# main.net
KiCad netlist of a schematic drawn in EAGLE
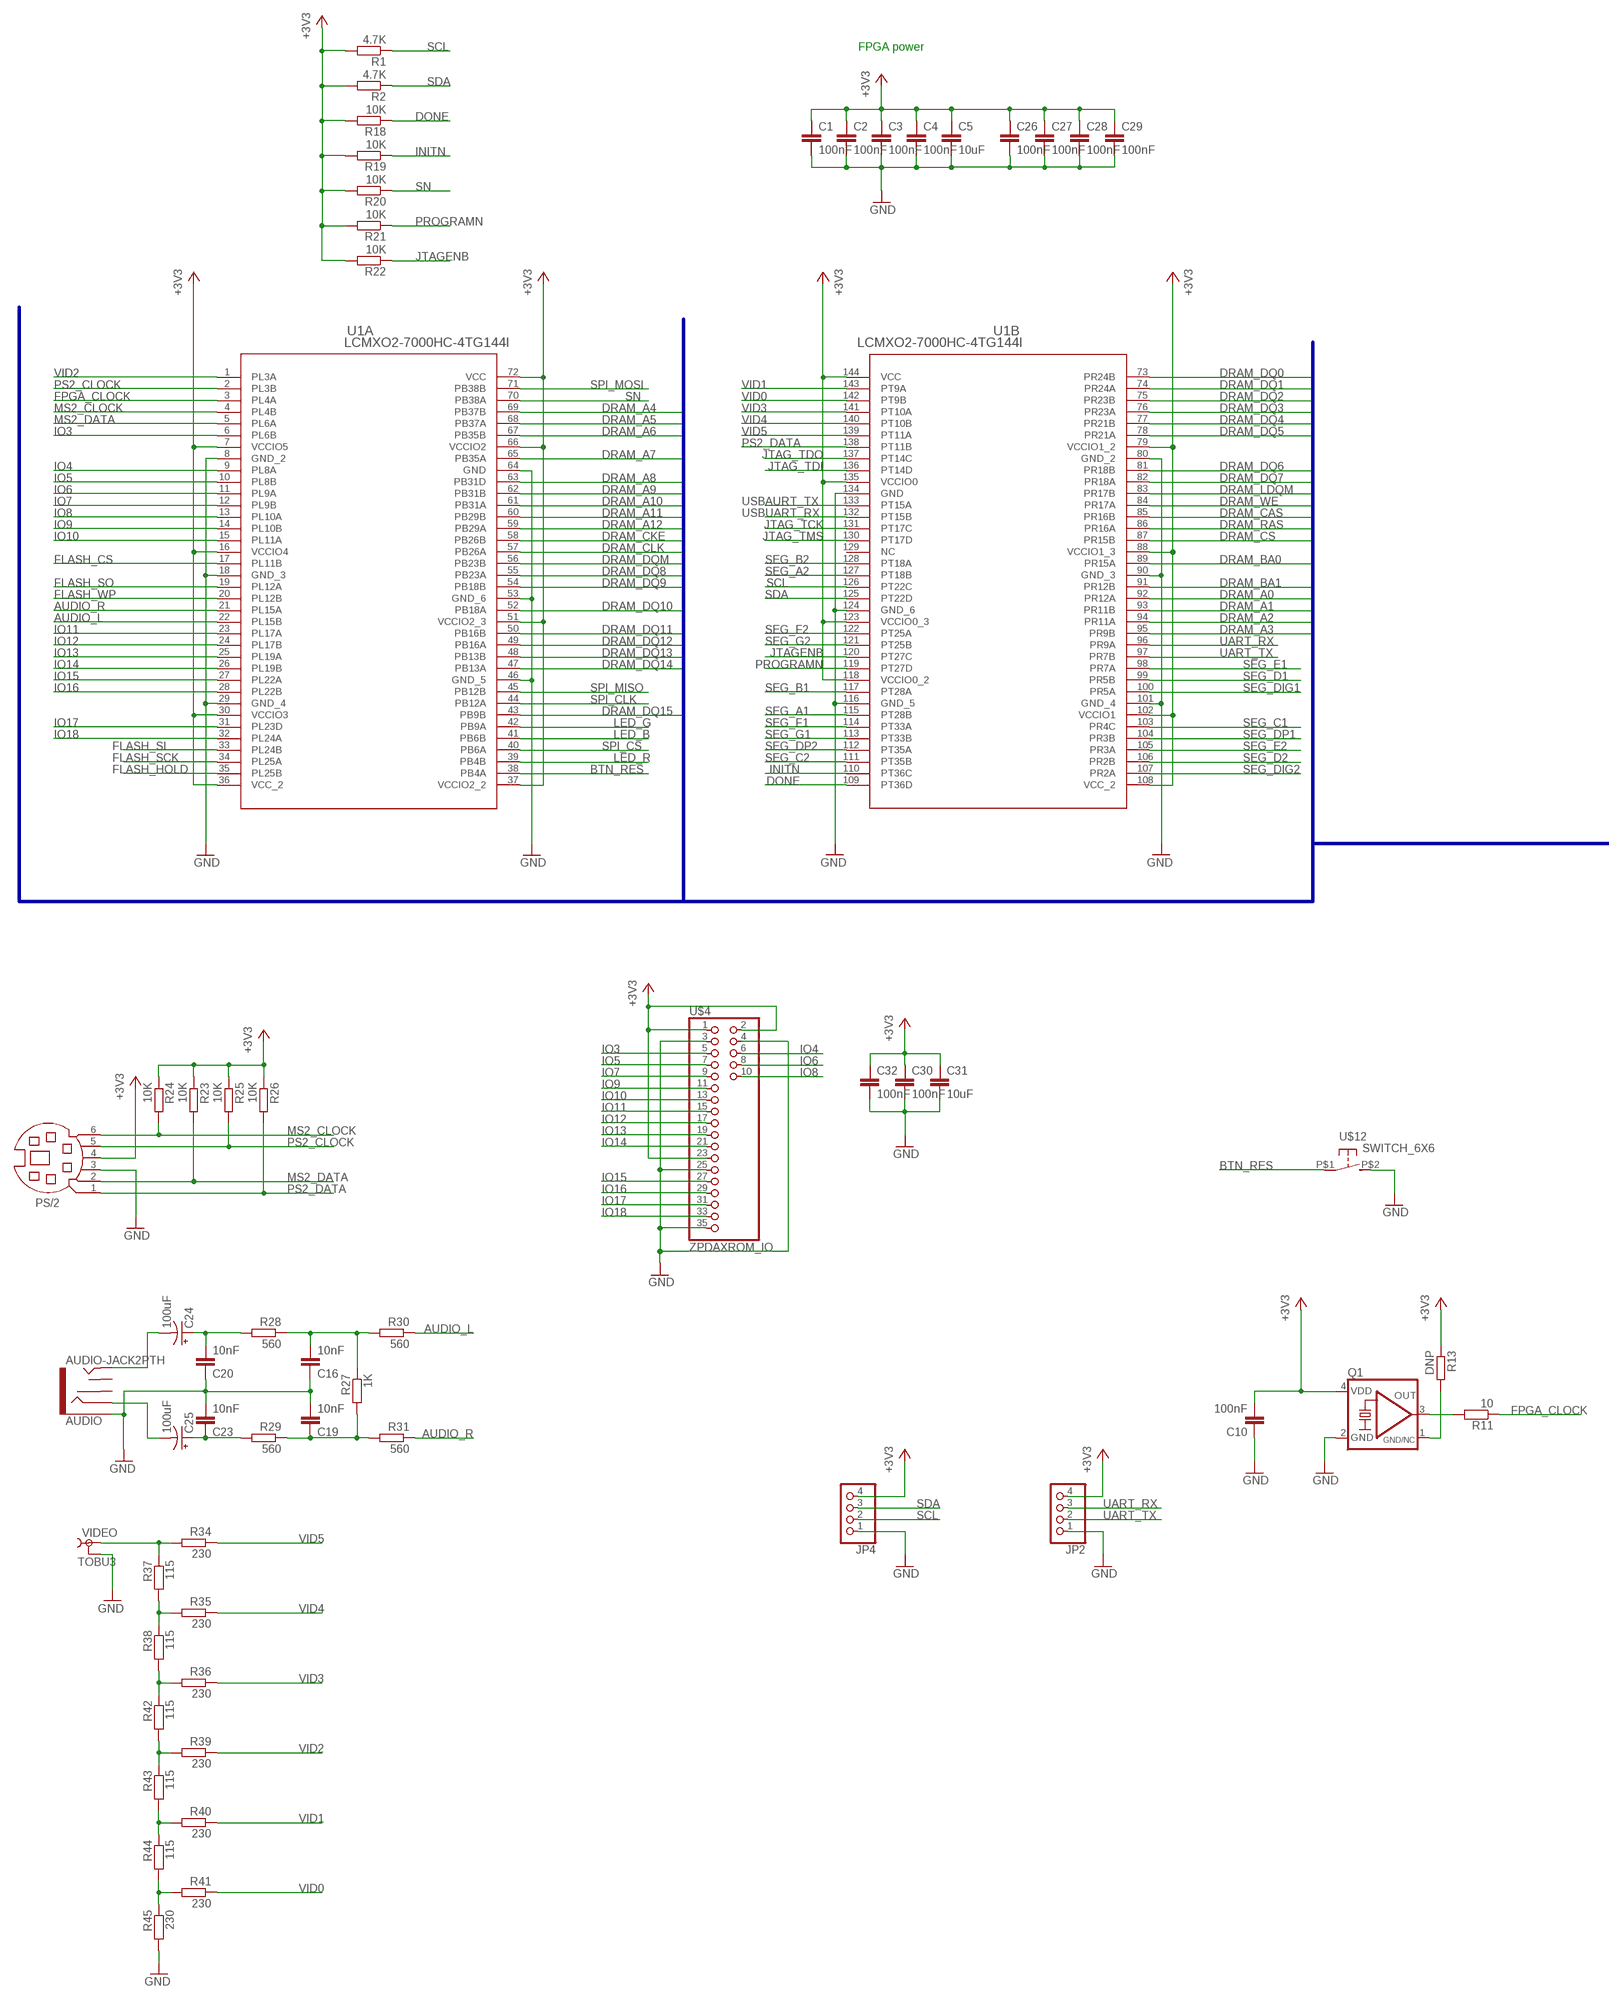
[diagram p0: schematic, sheet 1, part 1 of 2]
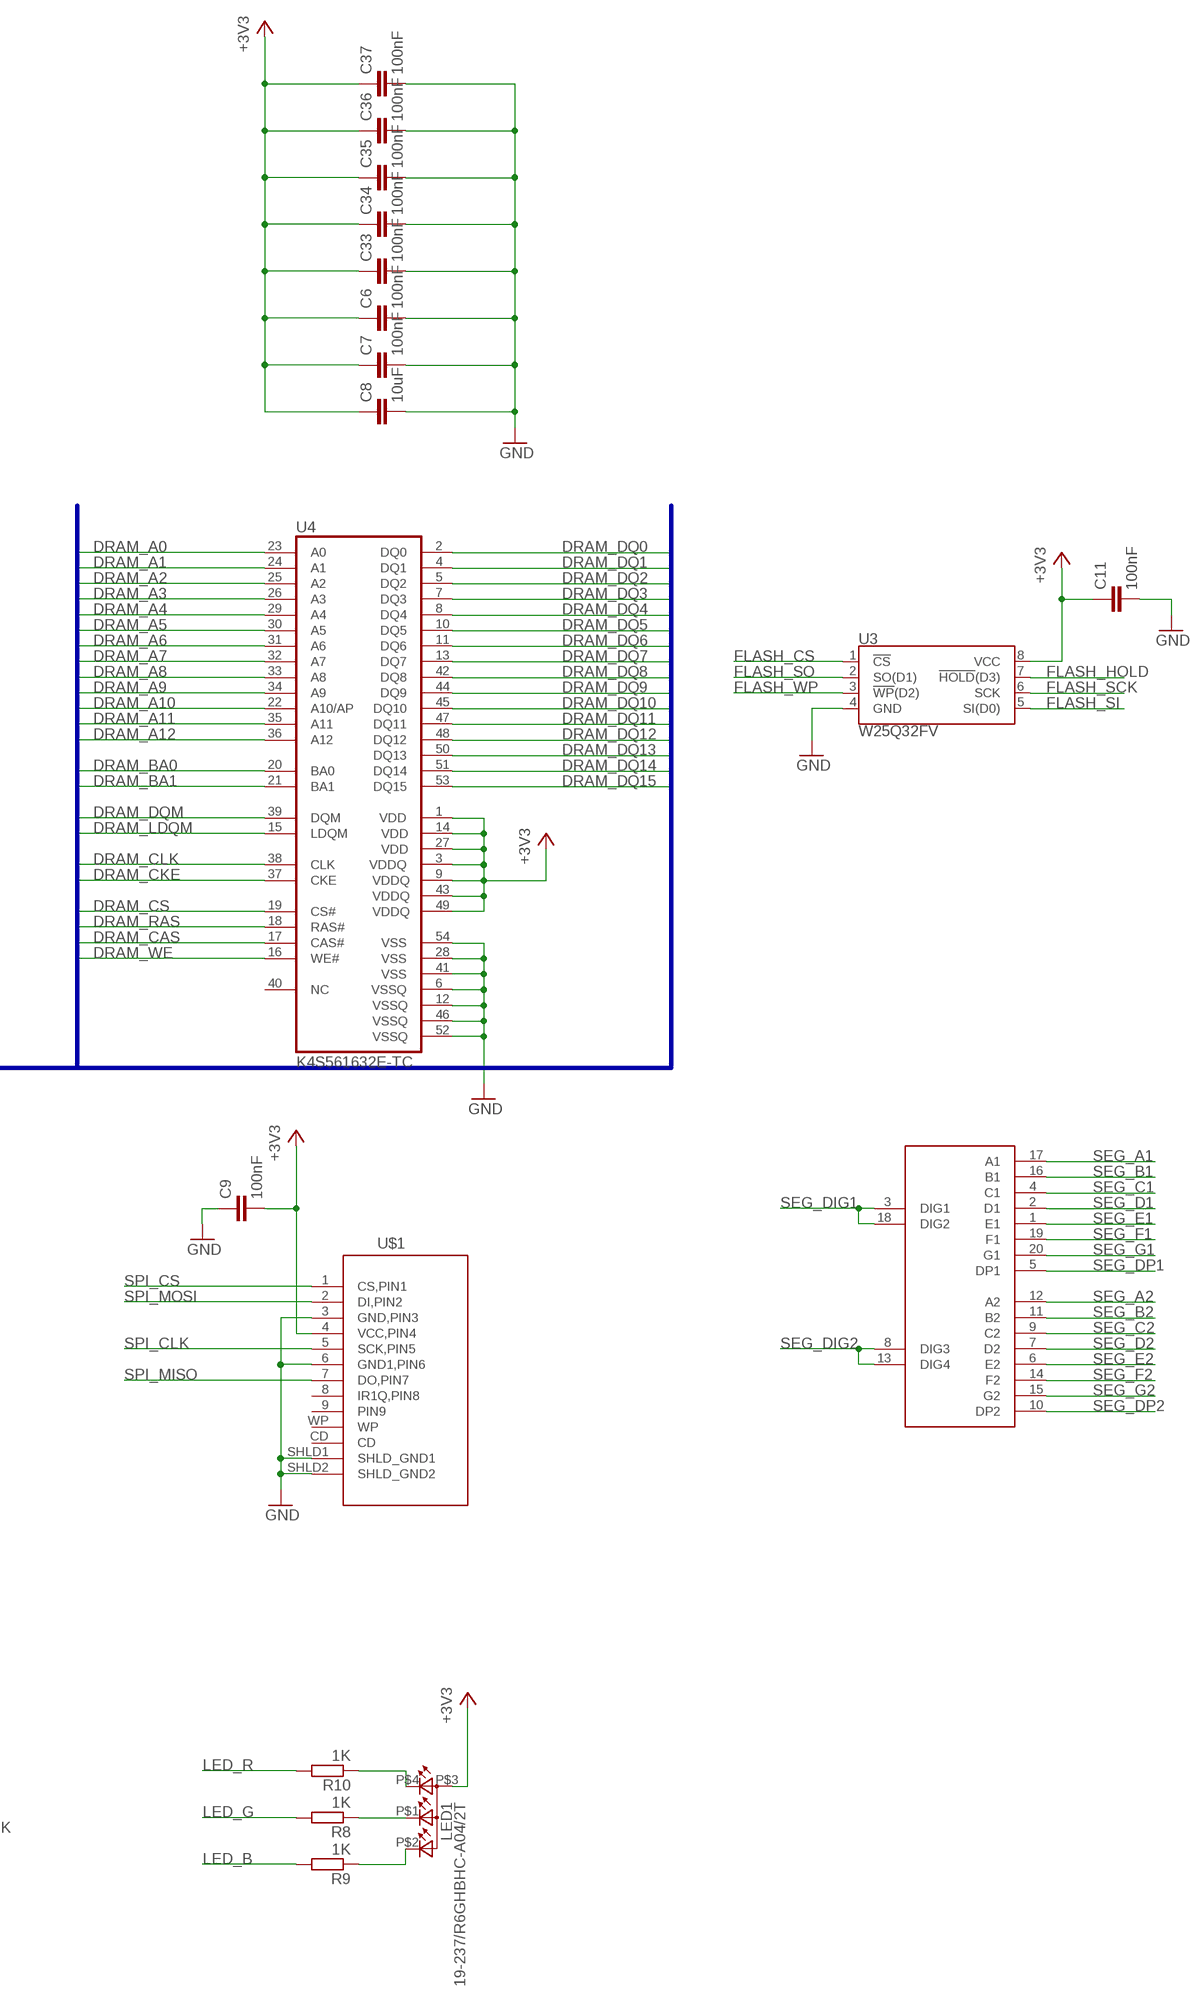
[diagram p1: schematic, sheet 1, part 2 of 2]
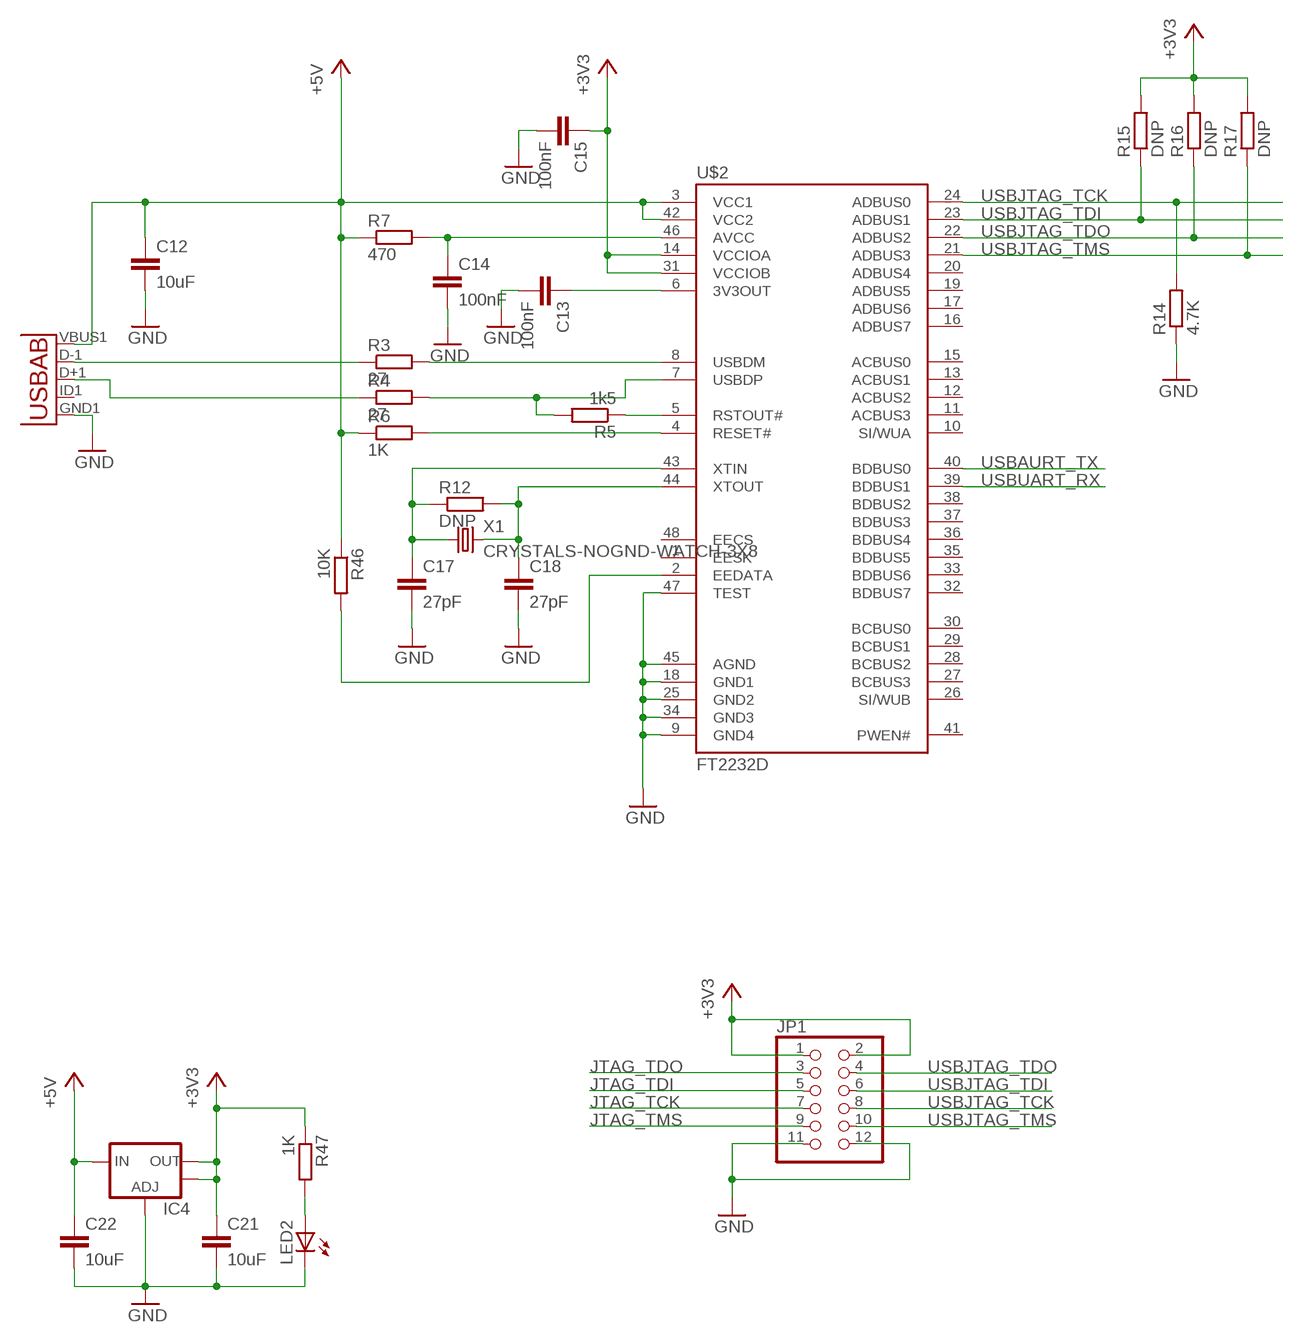
[diagram p2: schematic, sheet 2]

(export (version "E")
  (design (tool "Eeschema 10.0.6"))
  (components
    (comp (ref "C12")
      (value "10uF")
      (footprint "eagle-import:C0805")
      (libsource (lib "eagle-import") (part "C-EUC0805"))
    )
    (comp (ref "C13")
      (value "100nF")
      (footprint "eagle-import:C0603")
      (libsource (lib "eagle-import") (part "C-EUC0603"))
    )
    (comp (ref "C14")
      (value "100nF")
      (footprint "eagle-import:C0603")
      (libsource (lib "eagle-import") (part "C-EUC0603"))
    )
    (comp (ref "C15")
      (value "100nF")
      (footprint "eagle-import:C0603")
      (libsource (lib "eagle-import") (part "C-EUC0603"))
    )
    (comp (ref "C17")
      (value "27pF")
      (footprint "eagle-import:C0603")
      (libsource (lib "eagle-import") (part "C-EUC0603"))
    )
    (comp (ref "C18")
      (value "27pF")
      (footprint "eagle-import:C0603")
      (libsource (lib "eagle-import") (part "C-EUC0603"))
    )
    (comp (ref "C21")
      (value "10uF")
      (footprint "eagle-import:C0805")
      (libsource (lib "eagle-import") (part "C-EUC0805"))
    )
    (comp (ref "C22")
      (value "10uF")
      (footprint "eagle-import:C0805")
      (libsource (lib "eagle-import") (part "C-EUC0805"))
    )
    (comp (ref "IC4")
      (value "V_REG_LM1117SOT223")
      (footprint "eagle-import:SOT223")
      (libsource (lib "eagle-import") (part "V_REG_LM1117SOT223"))
    )
    (comp (ref "JP1")
      (value "PINHD-2X6")
      (footprint "eagle-import:2X06")
      (libsource (lib "eagle-import") (part "PINHD-2X6"))
    )
    (comp (ref "LED2")
      (value "LEDCHIPLED_0603")
      (footprint "eagle-import:CHIPLED_0603")
      (libsource (lib "eagle-import") (part "LEDCHIPLED_0603"))
    )
    (comp (ref "R3")
      (value "27")
      (footprint "eagle-import:R0603")
      (libsource (lib "eagle-import") (part "R-EU_R0603"))
    )
    (comp (ref "R4")
      (value "27")
      (footprint "eagle-import:R0603")
      (libsource (lib "eagle-import") (part "R-EU_R0603"))
    )
    (comp (ref "R5")
      (value "1k5")
      (footprint "eagle-import:R0603")
      (libsource (lib "eagle-import") (part "R-EU_R0603"))
    )
    (comp (ref "R6")
      (value "1K")
      (footprint "eagle-import:R0603")
      (libsource (lib "eagle-import") (part "R-EU_R0603"))
    )
    (comp (ref "R7")
      (value "470")
      (footprint "eagle-import:R0603")
      (libsource (lib "eagle-import") (part "R-EU_R0603"))
    )
    (comp (ref "R12")
      (value "DNP")
      (footprint "eagle-import:R0603")
      (libsource (lib "eagle-import") (part "R-EU_R0603"))
    )
    (comp (ref "R14")
      (value "4.7K")
      (footprint "eagle-import:R0603")
      (libsource (lib "eagle-import") (part "R-EU_R0603"))
    )
    (comp (ref "R15")
      (value "DNP")
      (footprint "eagle-import:R0603")
      (libsource (lib "eagle-import") (part "R-EU_R0603"))
    )
    (comp (ref "R16")
      (value "DNP")
      (footprint "eagle-import:R0603")
      (libsource (lib "eagle-import") (part "R-EU_R0603"))
    )
    (comp (ref "R17")
      (value "DNP")
      (footprint "eagle-import:R0603")
      (libsource (lib "eagle-import") (part "R-EU_R0603"))
    )
    (comp (ref "R46")
      (value "10K")
      (footprint "eagle-import:R0603")
      (libsource (lib "eagle-import") (part "R-EU_R0603"))
    )
    (comp (ref "R47")
      (value "1K")
      (footprint "eagle-import:R0603")
      (libsource (lib "eagle-import") (part "R-EU_R0603"))
    )
    (comp (ref "U$2")
      (value "FT2232D")
      (footprint "eagle-import:LQFP-48")
      (libsource (lib "eagle-import") (part "FT2232D"))
    )
    (comp (ref "U2")
      (value "USB\"\"")
      (footprint "eagle-import:USB-MICRO-SMD")
      (libsource (lib "eagle-import") (part "USB{dblquote}{dblquote}"))
    )
    (comp (ref "X1")
      (value "CRYSTALS-NOGND-WATCH-3X8")
      (footprint "eagle-import:WATCH-3X8")
      (libsource (lib "eagle-import") (part "CRYSTALS-NOGND-WATCH-3X8"))
    )
    (comp (ref "AUDIO")
      (value "AUDIO-JACK2PTH")
      (footprint "eagle-import:AUDIO-JACK")
      (libsource (lib "eagle-import") (part "AUDIO-JACK2PTH"))
    )
    (comp (ref "C1")
      (value "100nF")
      (footprint "eagle-import:C0603")
      (libsource (lib "eagle-import") (part "C-EUC0603"))
    )
    (comp (ref "C2")
      (value "100nF")
      (footprint "eagle-import:C0603")
      (libsource (lib "eagle-import") (part "C-EUC0603"))
    )
    (comp (ref "C3")
      (value "100nF")
      (footprint "eagle-import:C0603")
      (libsource (lib "eagle-import") (part "C-EUC0603"))
    )
    (comp (ref "C4")
      (value "100nF")
      (footprint "eagle-import:C0603")
      (libsource (lib "eagle-import") (part "C-EUC0603"))
    )
    (comp (ref "C5")
      (value "10uF")
      (footprint "eagle-import:C0805")
      (libsource (lib "eagle-import") (part "C-EUC0805"))
    )
    (comp (ref "C6")
      (value "100nF")
      (footprint "eagle-import:C0603")
      (libsource (lib "eagle-import") (part "C-EUC0603"))
    )
    (comp (ref "C7")
      (value "100nF")
      (footprint "eagle-import:C0603")
      (libsource (lib "eagle-import") (part "C-EUC0603"))
    )
    (comp (ref "C8")
      (value "10uF")
      (footprint "eagle-import:C0805")
      (libsource (lib "eagle-import") (part "C-EUC0805"))
    )
    (comp (ref "C9")
      (value "100nF")
      (footprint "eagle-import:C0603")
      (libsource (lib "eagle-import") (part "C-EUC0603"))
    )
    (comp (ref "C10")
      (value "100nF")
      (footprint "eagle-import:C0603")
      (libsource (lib "eagle-import") (part "C-EUC0603"))
    )
    (comp (ref "C11")
      (value "100nF")
      (footprint "eagle-import:C0603")
      (libsource (lib "eagle-import") (part "C-EUC0603"))
    )
    (comp (ref "C16")
      (value "10nF")
      (footprint "eagle-import:C0603")
      (libsource (lib "eagle-import") (part "C-EUC0603"))
    )
    (comp (ref "C19")
      (value "10nF")
      (footprint "eagle-import:C0603")
      (libsource (lib "eagle-import") (part "C-EUC0603"))
    )
    (comp (ref "C20")
      (value "10nF")
      (footprint "eagle-import:C0603")
      (libsource (lib "eagle-import") (part "C-EUC0603"))
    )
    (comp (ref "C23")
      (value "10nF")
      (footprint "eagle-import:C0603")
      (libsource (lib "eagle-import") (part "C-EUC0603"))
    )
    (comp (ref "C24")
      (value "100uF")
      (footprint "eagle-import:EIA7343")
      (libsource (lib "eagle-import") (part "CAP_POL7343"))
    )
    (comp (ref "C25")
      (value "100uF")
      (footprint "eagle-import:EIA7343")
      (libsource (lib "eagle-import") (part "CAP_POL7343"))
    )
    (comp (ref "C26")
      (value "100nF")
      (footprint "eagle-import:C0603")
      (libsource (lib "eagle-import") (part "C-EUC0603"))
    )
    (comp (ref "C27")
      (value "100nF")
      (footprint "eagle-import:C0603")
      (libsource (lib "eagle-import") (part "C-EUC0603"))
    )
    (comp (ref "C28")
      (value "100nF")
      (footprint "eagle-import:C0603")
      (libsource (lib "eagle-import") (part "C-EUC0603"))
    )
    (comp (ref "C29")
      (value "100nF")
      (footprint "eagle-import:C0603")
      (libsource (lib "eagle-import") (part "C-EUC0603"))
    )
    (comp (ref "C30")
      (value "100nF")
      (footprint "eagle-import:C0603")
      (libsource (lib "eagle-import") (part "C-EUC0603"))
    )
    (comp (ref "C31")
      (value "10uF")
      (footprint "eagle-import:C0805")
      (libsource (lib "eagle-import") (part "C-EUC0805"))
    )
    (comp (ref "C32")
      (value "100nF")
      (footprint "eagle-import:C0603")
      (libsource (lib "eagle-import") (part "C-EUC0603"))
    )
    (comp (ref "C33")
      (value "100nF")
      (footprint "eagle-import:C0603")
      (libsource (lib "eagle-import") (part "C-EUC0603"))
    )
    (comp (ref "C34")
      (value "100nF")
      (footprint "eagle-import:C0603")
      (libsource (lib "eagle-import") (part "C-EUC0603"))
    )
    (comp (ref "C35")
      (value "100nF")
      (footprint "eagle-import:C0603")
      (libsource (lib "eagle-import") (part "C-EUC0603"))
    )
    (comp (ref "C36")
      (value "100nF")
      (footprint "eagle-import:C0603")
      (libsource (lib "eagle-import") (part "C-EUC0603"))
    )
    (comp (ref "C37")
      (value "100nF")
      (footprint "eagle-import:C0603")
      (libsource (lib "eagle-import") (part "C-EUC0603"))
    )
    (comp (ref "JP2")
      (value "PINHD-1X4")
      (footprint "eagle-import:1X04")
      (libsource (lib "eagle-import") (part "PINHD-1X4"))
    )
    (comp (ref "JP4")
      (value "PINHD-1X4")
      (footprint "eagle-import:1X04")
      (libsource (lib "eagle-import") (part "PINHD-1X4"))
    )
    (comp (ref "LED1")
      (value "19-237/R6GHBHC-A04/2T")
      (footprint "eagle-import:19-237_R6GHBHC-A04_2T")
      (libsource (lib "eagle-import") (part "19-237/R6GHBHC-A04/2T"))
    )
    (comp (ref "PS/2")
      (value "MD06SS")
      (footprint "eagle-import:MDIN06SS")
      (libsource (lib "eagle-import") (part "MD06SS"))
    )
    (comp (ref "Q1")
      (value "KXO-TCXO-CMOS-82")
      (footprint "eagle-import:7.0X5.0_KXO-82-TCXO")
      (libsource (lib "eagle-import") (part "KXO-TCXO-CMOS-82"))
    )
    (comp (ref "R1")
      (value "4.7K")
      (footprint "eagle-import:R0603")
      (libsource (lib "eagle-import") (part "R-EU_R0603"))
    )
    (comp (ref "R2")
      (value "4.7K")
      (footprint "eagle-import:R0603")
      (libsource (lib "eagle-import") (part "R-EU_R0603"))
    )
    (comp (ref "R8")
      (value "1K")
      (footprint "eagle-import:R0603")
      (libsource (lib "eagle-import") (part "R-EU_R0603"))
    )
    (comp (ref "R9")
      (value "1K")
      (footprint "eagle-import:R0603")
      (libsource (lib "eagle-import") (part "R-EU_R0603"))
    )
    (comp (ref "R10")
      (value "1K")
      (footprint "eagle-import:R0603")
      (libsource (lib "eagle-import") (part "R-EU_R0603"))
    )
    (comp (ref "R11")
      (value "10")
      (footprint "eagle-import:R0603")
      (libsource (lib "eagle-import") (part "R-EU_R0603"))
    )
    (comp (ref "R13")
      (value "DNP")
      (footprint "eagle-import:R0603")
      (libsource (lib "eagle-import") (part "R-EU_R0603"))
    )
    (comp (ref "R18")
      (value "10K")
      (footprint "eagle-import:R0603")
      (libsource (lib "eagle-import") (part "R-EU_R0603"))
    )
    (comp (ref "R19")
      (value "10K")
      (footprint "eagle-import:R0603")
      (libsource (lib "eagle-import") (part "R-EU_R0603"))
    )
    (comp (ref "R20")
      (value "10K")
      (footprint "eagle-import:R0603")
      (libsource (lib "eagle-import") (part "R-EU_R0603"))
    )
    (comp (ref "R21")
      (value "10K")
      (footprint "eagle-import:R0603")
      (libsource (lib "eagle-import") (part "R-EU_R0603"))
    )
    (comp (ref "R22")
      (value "10K")
      (footprint "eagle-import:R0603")
      (libsource (lib "eagle-import") (part "R-EU_R0603"))
    )
    (comp (ref "R23")
      (value "10K")
      (footprint "eagle-import:R0603")
      (libsource (lib "eagle-import") (part "R-EU_R0603"))
    )
    (comp (ref "R24")
      (value "10K")
      (footprint "eagle-import:R0603")
      (libsource (lib "eagle-import") (part "R-EU_R0603"))
    )
    (comp (ref "R25")
      (value "10K")
      (footprint "eagle-import:R0603")
      (libsource (lib "eagle-import") (part "R-EU_R0603"))
    )
    (comp (ref "R26")
      (value "10K")
      (footprint "eagle-import:R0603")
      (libsource (lib "eagle-import") (part "R-EU_R0603"))
    )
    (comp (ref "R27")
      (value "1K")
      (footprint "eagle-import:R0603")
      (libsource (lib "eagle-import") (part "R-EU_R0603"))
    )
    (comp (ref "R28")
      (value "560")
      (footprint "eagle-import:R0603")
      (libsource (lib "eagle-import") (part "R-EU_R0603"))
    )
    (comp (ref "R29")
      (value "560")
      (footprint "eagle-import:R0603")
      (libsource (lib "eagle-import") (part "R-EU_R0603"))
    )
    (comp (ref "R30")
      (value "560")
      (footprint "eagle-import:R0603")
      (libsource (lib "eagle-import") (part "R-EU_R0603"))
    )
    (comp (ref "R31")
      (value "560")
      (footprint "eagle-import:R0603")
      (libsource (lib "eagle-import") (part "R-EU_R0603"))
    )
    (comp (ref "R34")
      (value "230")
      (footprint "eagle-import:R0603")
      (libsource (lib "eagle-import") (part "R-EU_R0603"))
    )
    (comp (ref "R35")
      (value "230")
      (footprint "eagle-import:R0603")
      (libsource (lib "eagle-import") (part "R-EU_R0603"))
    )
    (comp (ref "R36")
      (value "230")
      (footprint "eagle-import:R0603")
      (libsource (lib "eagle-import") (part "R-EU_R0603"))
    )
    (comp (ref "R37")
      (value "115")
      (footprint "eagle-import:R0603")
      (libsource (lib "eagle-import") (part "R-EU_R0603"))
    )
    (comp (ref "R38")
      (value "115")
      (footprint "eagle-import:R0603")
      (libsource (lib "eagle-import") (part "R-EU_R0603"))
    )
    (comp (ref "R39")
      (value "230")
      (footprint "eagle-import:R0603")
      (libsource (lib "eagle-import") (part "R-EU_R0603"))
    )
    (comp (ref "R40")
      (value "230")
      (footprint "eagle-import:R0603")
      (libsource (lib "eagle-import") (part "R-EU_R0603"))
    )
    (comp (ref "R41")
      (value "230")
      (footprint "eagle-import:R0603")
      (libsource (lib "eagle-import") (part "R-EU_R0603"))
    )
    (comp (ref "R42")
      (value "115")
      (footprint "eagle-import:R0603")
      (libsource (lib "eagle-import") (part "R-EU_R0603"))
    )
    (comp (ref "R43")
      (value "115")
      (footprint "eagle-import:R0603")
      (libsource (lib "eagle-import") (part "R-EU_R0603"))
    )
    (comp (ref "R44")
      (value "115")
      (footprint "eagle-import:R0603")
      (libsource (lib "eagle-import") (part "R-EU_R0603"))
    )
    (comp (ref "R45")
      (value "230")
      (footprint "eagle-import:R0603")
      (libsource (lib "eagle-import") (part "R-EU_R0603"))
    )
    (comp (ref "U$1")
      (value "FCI_SD_SOCKET")
      (footprint "eagle-import:SD-MMC_SOCKET-PP")
      (fields (field (name "MF") "FCI") (field (name "MPN") "10067847-001RLF"))
      (libsource (lib "eagle-import") (part "FCI_SD_SOCKET"))
    )
    (comp (ref "U$3")
      (value "GS2020CR-G")
      (footprint "eagle-import:GS2020CR")
      (libsource (lib "eagle-import") (part "GS2020CR-G"))
    )
    (comp (ref "U$4")
      (value "ZPDAXROM_IO")
      (footprint "eagle-import:2X18_ZPDAXROM_IO")
      (libsource (lib "eagle-import") (part "ZPDAXROM_IO"))
    )
    (comp (ref "U$12")
      (value "SWITCH_6X6")
      (footprint "eagle-import:SWITCH_6X6")
      (libsource (lib "eagle-import") (part "SWITCH_6X6"))
    )
    (comp (ref "U1")
      (value "LCMXO2-7000HC-4TG144I")
      (footprint "eagle-import:TQFP144")
      (fields (field (name "MANUFACTURER_PART_NUMBER") "LCMXO27000HC4TG144I"))
      (libsource (lib "eagle-import") (part "LCMXO2-7000HC-4TG144I"))
    )
    (comp (ref "U3")
      (value "W25Q32FV")
      (footprint "eagle-import:SOIC-8")
      (libsource (lib "eagle-import") (part "W25Q32FVSS"))
    )
    (comp (ref "U4")
      (value "K4S561632E-TC")
      (footprint "eagle-import:TSOP54")
      (libsource (lib "eagle-import") (part "K4S561632E-TC"))
    )
    (comp (ref "VIDEO")
      (value "TOBU3")
      (footprint "eagle-import:TOBU3")
      (fields (field (name "MF") "FARNELL") (field (name "MPN") "TOBU 3"))
      (libsource (lib "eagle-import") (part "TOBU3"))
    )
  )
  (nets
    (net (code "1") (name "+3V3") (class "Default")
      (node (ref "C1") (pin "1") (pinfunction "1_1") (pintype "passive"))
      (node (ref "C10") (pin "2") (pinfunction "2_2") (pintype "passive"))
      (node (ref "C11") (pin "1") (pinfunction "1_1") (pintype "passive"))
      (node (ref "C15") (pin "1") (pinfunction "1_1") (pintype "passive"))
      (node (ref "C2") (pin "1") (pinfunction "1_1") (pintype "passive"))
      (node (ref "C21") (pin "1") (pinfunction "1_1") (pintype "passive"))
      (node (ref "C26") (pin "1") (pinfunction "1_1") (pintype "passive"))
      (node (ref "C27") (pin "1") (pinfunction "1_1") (pintype "passive"))
      (node (ref "C28") (pin "1") (pinfunction "1_1") (pintype "passive"))
      (node (ref "C29") (pin "1") (pinfunction "1_1") (pintype "passive"))
      (node (ref "C3") (pin "1") (pinfunction "1_1") (pintype "passive"))
      (node (ref "C30") (pin "1") (pinfunction "1_1") (pintype "passive"))
      (node (ref "C31") (pin "1") (pinfunction "1_1") (pintype "passive"))
      (node (ref "C32") (pin "1") (pinfunction "1_1") (pintype "passive"))
      (node (ref "C33") (pin "1") (pinfunction "1_1") (pintype "passive"))
      (node (ref "C34") (pin "1") (pinfunction "1_1") (pintype "passive"))
      (node (ref "C35") (pin "1") (pinfunction "1_1") (pintype "passive"))
      (node (ref "C36") (pin "1") (pinfunction "1_1") (pintype "passive"))
      (node (ref "C37") (pin "1") (pinfunction "1_1") (pintype "passive"))
      (node (ref "C4") (pin "1") (pinfunction "1_1") (pintype "passive"))
      (node (ref "C5") (pin "1") (pinfunction "1_1") (pintype "passive"))
      (node (ref "C6") (pin "1") (pinfunction "1_1") (pintype "passive"))
      (node (ref "C7") (pin "1") (pinfunction "1_1") (pintype "passive"))
      (node (ref "C8") (pin "1") (pinfunction "1_1") (pintype "passive"))
      (node (ref "C9") (pin "2") (pinfunction "2_2") (pintype "passive"))
      (node (ref "IC4") (pin "2") (pinfunction "OUT_2") (pintype "output"))
      (node (ref "IC4") (pin "4") (pinfunction "OUT_4") (pintype "output"))
      (node (ref "JP1") (pin "1") (pinfunction "1_1") (pintype "passive"))
      (node (ref "JP1") (pin "2") (pinfunction "2_2") (pintype "passive"))
      (node (ref "JP2") (pin "4") (pinfunction "4_4") (pintype "passive"))
      (node (ref "JP4") (pin "4") (pinfunction "4_4") (pintype "passive"))
      (node (ref "LED1") (pin "P$3") (pinfunction "A_P$3") (pintype "passive"))
      (node (ref "PS/2") (pin "4") (pinfunction "4_4") (pintype "passive"))
      (node (ref "Q1") (pin "4") (pinfunction "VDD_4") (pintype "power_in"))
      (node (ref "R1") (pin "2") (pinfunction "2_2") (pintype "passive"))
      (node (ref "R13") (pin "1") (pinfunction "1_1") (pintype "passive"))
      (node (ref "R15") (pin "2") (pinfunction "2_2") (pintype "passive"))
      (node (ref "R16") (pin "2") (pinfunction "2_2") (pintype "passive"))
      (node (ref "R17") (pin "2") (pinfunction "2_2") (pintype "passive"))
      (node (ref "R18") (pin "2") (pinfunction "2_2") (pintype "passive"))
      (node (ref "R19") (pin "2") (pinfunction "2_2") (pintype "passive"))
      (node (ref "R2") (pin "2") (pinfunction "2_2") (pintype "passive"))
      (node (ref "R20") (pin "2") (pinfunction "2_2") (pintype "passive"))
      (node (ref "R21") (pin "2") (pinfunction "2_2") (pintype "passive"))
      (node (ref "R22") (pin "2") (pinfunction "2_2") (pintype "passive"))
      (node (ref "R23") (pin "1") (pinfunction "1_1") (pintype "passive"))
      (node (ref "R24") (pin "1") (pinfunction "1_1") (pintype "passive"))
      (node (ref "R25") (pin "1") (pinfunction "1_1") (pintype "passive"))
      (node (ref "R26") (pin "1") (pinfunction "1_1") (pintype "passive"))
      (node (ref "R47") (pin "1") (pinfunction "1_1") (pintype "passive"))
      (node (ref "U$1") (pin "4") (pinfunction "VCC,PIN4_4") (pintype "bidirectional"))
      (node (ref "U$2") (pin "14") (pinfunction "VCCIOA_14") (pintype "power_in"))
      (node (ref "U$2") (pin "31") (pinfunction "VCCIOB_31") (pintype "bidirectional"))
      (node (ref "U$4") (pin "1") (pinfunction "1_1") (pintype "passive"))
      (node (ref "U$4") (pin "2") (pinfunction "2_2") (pintype "passive"))
      (node (ref "U$4") (pin "23") (pinfunction "23_23") (pintype "passive"))
      (node (ref "U1") (pin "102") (pinfunction "VCCIO1_102") (pintype "power_in"))
      (node (ref "U1") (pin "108") (pinfunction "VCC_2_108") (pintype "power_in"))
      (node (ref "U1") (pin "118") (pinfunction "VCCIO0_2_118") (pintype "power_in"))
      (node (ref "U1") (pin "123") (pinfunction "VCCIO0_3_123") (pintype "power_in"))
      (node (ref "U1") (pin "135") (pinfunction "VCCIO0_135") (pintype "power_in"))
      (node (ref "U1") (pin "144") (pinfunction "VCC_144") (pintype "power_in"))
      (node (ref "U1") (pin "16") (pinfunction "VCCIO4_16") (pintype "power_in"))
      (node (ref "U1") (pin "30") (pinfunction "VCCIO3_30") (pintype "power_in"))
      (node (ref "U1") (pin "36") (pinfunction "VCC_2_36") (pintype "power_in"))
      (node (ref "U1") (pin "37") (pinfunction "VCCIO2_2_37") (pintype "power_in"))
      (node (ref "U1") (pin "51") (pinfunction "VCCIO2_3_51") (pintype "power_in"))
      (node (ref "U1") (pin "66") (pinfunction "VCCIO2_66") (pintype "power_in"))
      (node (ref "U1") (pin "7") (pinfunction "VCCIO5_7") (pintype "power_in"))
      (node (ref "U1") (pin "72") (pinfunction "VCC_72") (pintype "power_in"))
      (node (ref "U1") (pin "79") (pinfunction "VCCIO1_2_79") (pintype "power_in"))
      (node (ref "U1") (pin "88") (pinfunction "VCCIO1_3_88") (pintype "power_in"))
      (node (ref "U3") (pin "8") (pinfunction "VCC_8") (pintype "bidirectional"))
      (node (ref "U4") (pin "1") (pinfunction "VDD_1") (pintype "power_in"))
      (node (ref "U4") (pin "14") (pinfunction "VDD_14") (pintype "power_in"))
      (node (ref "U4") (pin "27") (pinfunction "VDD_27") (pintype "power_in"))
      (node (ref "U4") (pin "3") (pinfunction "VDDQ_3") (pintype "power_in"))
      (node (ref "U4") (pin "43") (pinfunction "VDDQ_43") (pintype "power_in"))
      (node (ref "U4") (pin "49") (pinfunction "VDDQ_49") (pintype "power_in"))
      (node (ref "U4") (pin "9") (pinfunction "VDDQ_9") (pintype "power_in"))
    )
    (net (code "2") (name "+5V") (class "Default")
      (node (ref "C12") (pin "1") (pinfunction "1_1") (pintype "passive"))
      (node (ref "C22") (pin "1") (pinfunction "1_1") (pintype "passive"))
      (node (ref "IC4") (pin "3") (pinfunction "IN_3") (pintype "input"))
      (node (ref "R46") (pin "1") (pinfunction "1_1") (pintype "passive"))
      (node (ref "R6") (pin "1") (pinfunction "1_1") (pintype "passive"))
      (node (ref "R7") (pin "1") (pinfunction "1_1") (pintype "passive"))
      (node (ref "U$2") (pin "3") (pinfunction "VCC1_3") (pintype "power_in"))
      (node (ref "U$2") (pin "42") (pinfunction "VCC2_42") (pintype "power_in"))
      (node (ref "U2") (pin "VBUS1") (pinfunction "VBUS_VBUS1") (pintype "bidirectional"))
    )
    (net (code "3") (name "AUDIO_L") (class "Default")
      (node (ref "R30") (pin "1") (pinfunction "1_1") (pintype "passive"))
      (node (ref "U1") (pin "22") (pinfunction "PL15B_22") (pintype "passive"))
    )
    (net (code "4") (name "AUDIO_R") (class "Default")
      (node (ref "R31") (pin "1") (pinfunction "1_1") (pintype "passive"))
      (node (ref "U1") (pin "21") (pinfunction "PL15A_21") (pintype "passive"))
    )
    (net (code "5") (name "BTN_RES") (class "Default")
      (node (ref "U$12") (pin "P$1") (pinfunction "P_P$1") (pintype "passive"))
      (node (ref "U1") (pin "38") (pinfunction "PB4A_38") (pintype "passive"))
    )
    (net (code "6") (name "DONE") (class "Default")
      (node (ref "R18") (pin "1") (pinfunction "1_1") (pintype "passive"))
      (node (ref "U1") (pin "109") (pinfunction "PT36D_109") (pintype "passive"))
    )
    (net (code "7") (name "DRAM_A0") (class "Default")
      (node (ref "U1") (pin "92") (pinfunction "PR12A_92") (pintype "passive"))
      (node (ref "U4") (pin "23") (pinfunction "A0_23") (pintype "input"))
    )
    (net (code "8") (name "DRAM_A1") (class "Default")
      (node (ref "U1") (pin "93") (pinfunction "PR11B_93") (pintype "passive"))
      (node (ref "U4") (pin "24") (pinfunction "A1_24") (pintype "input"))
    )
    (net (code "9") (name "DRAM_A2") (class "Default")
      (node (ref "U1") (pin "94") (pinfunction "PR11A_94") (pintype "passive"))
      (node (ref "U4") (pin "25") (pinfunction "A2_25") (pintype "input"))
    )
    (net (code "10") (name "DRAM_A3") (class "Default")
      (node (ref "U1") (pin "95") (pinfunction "PR9B_95") (pintype "passive"))
      (node (ref "U4") (pin "26") (pinfunction "A3_26") (pintype "input"))
    )
    (net (code "11") (name "DRAM_A4") (class "Default")
      (node (ref "U1") (pin "69") (pinfunction "PB37B_69") (pintype "passive"))
      (node (ref "U4") (pin "29") (pinfunction "A4_29") (pintype "input"))
    )
    (net (code "12") (name "DRAM_A5") (class "Default")
      (node (ref "U1") (pin "68") (pinfunction "PB37A_68") (pintype "passive"))
      (node (ref "U4") (pin "30") (pinfunction "A5_30") (pintype "input"))
    )
    (net (code "13") (name "DRAM_A6") (class "Default")
      (node (ref "U1") (pin "67") (pinfunction "PB35B_67") (pintype "passive"))
      (node (ref "U4") (pin "31") (pinfunction "A6_31") (pintype "input"))
    )
    (net (code "14") (name "DRAM_A7") (class "Default")
      (node (ref "U1") (pin "65") (pinfunction "PB35A_65") (pintype "passive"))
      (node (ref "U4") (pin "32") (pinfunction "A7_32") (pintype "input"))
    )
    (net (code "15") (name "DRAM_A8") (class "Default")
      (node (ref "U1") (pin "63") (pinfunction "PB31D_63") (pintype "passive"))
      (node (ref "U4") (pin "33") (pinfunction "A8_33") (pintype "input"))
    )
    (net (code "16") (name "DRAM_A9") (class "Default")
      (node (ref "U1") (pin "62") (pinfunction "PB31B_62") (pintype "passive"))
      (node (ref "U4") (pin "34") (pinfunction "A9_34") (pintype "input"))
    )
    (net (code "17") (name "DRAM_A10") (class "Default")
      (node (ref "U1") (pin "61") (pinfunction "PB31A_61") (pintype "passive"))
      (node (ref "U4") (pin "22") (pinfunction "A10/AP_22") (pintype "input"))
    )
    (net (code "18") (name "DRAM_A11") (class "Default")
      (node (ref "U1") (pin "60") (pinfunction "PB29B_60") (pintype "passive"))
      (node (ref "U4") (pin "35") (pinfunction "A11_35") (pintype "input"))
    )
    (net (code "19") (name "DRAM_A12") (class "Default")
      (node (ref "U1") (pin "59") (pinfunction "PB29A_59") (pintype "passive"))
      (node (ref "U4") (pin "36") (pinfunction "A12_36") (pintype "input"))
    )
    (net (code "20") (name "DRAM_BA0") (class "Default")
      (node (ref "U1") (pin "89") (pinfunction "PR15A_89") (pintype "passive"))
      (node (ref "U4") (pin "20") (pinfunction "BA0_20") (pintype "input"))
    )
    (net (code "21") (name "DRAM_BA1") (class "Default")
      (node (ref "U1") (pin "91") (pinfunction "PR12B_91") (pintype "passive"))
      (node (ref "U4") (pin "21") (pinfunction "BA1_21") (pintype "input"))
    )
    (net (code "22") (name "DRAM_CAS") (class "Default")
      (node (ref "U1") (pin "85") (pinfunction "PR16B_85") (pintype "passive"))
      (node (ref "U4") (pin "17") (pinfunction "CAS#_17") (pintype "input"))
    )
    (net (code "23") (name "DRAM_CKE") (class "Default")
      (node (ref "U1") (pin "58") (pinfunction "PB26B_58") (pintype "passive"))
      (node (ref "U4") (pin "37") (pinfunction "CKE_37") (pintype "input"))
    )
    (net (code "24") (name "DRAM_CLK") (class "Default")
      (node (ref "U1") (pin "57") (pinfunction "PB26A_57") (pintype "passive"))
      (node (ref "U4") (pin "38") (pinfunction "CLK_38") (pintype "input"))
    )
    (net (code "25") (name "DRAM_CS") (class "Default")
      (node (ref "U1") (pin "87") (pinfunction "PR15B_87") (pintype "passive"))
      (node (ref "U4") (pin "19") (pinfunction "CS#_19") (pintype "input"))
    )
    (net (code "26") (name "DRAM_DQ0") (class "Default")
      (node (ref "U1") (pin "73") (pinfunction "PR24B_73") (pintype "passive"))
      (node (ref "U4") (pin "2") (pinfunction "DQ0_2") (pintype "bidirectional"))
    )
    (net (code "27") (name "DRAM_DQ1") (class "Default")
      (node (ref "U1") (pin "74") (pinfunction "PR24A_74") (pintype "passive"))
      (node (ref "U4") (pin "4") (pinfunction "DQ1_4") (pintype "bidirectional"))
    )
    (net (code "28") (name "DRAM_DQ2") (class "Default")
      (node (ref "U1") (pin "75") (pinfunction "PR23B_75") (pintype "passive"))
      (node (ref "U4") (pin "5") (pinfunction "DQ2_5") (pintype "bidirectional"))
    )
    (net (code "29") (name "DRAM_DQ3") (class "Default")
      (node (ref "U1") (pin "76") (pinfunction "PR23A_76") (pintype "passive"))
      (node (ref "U4") (pin "7") (pinfunction "DQ3_7") (pintype "bidirectional"))
    )
    (net (code "30") (name "DRAM_DQ4") (class "Default")
      (node (ref "U1") (pin "77") (pinfunction "PR21B_77") (pintype "passive"))
      (node (ref "U4") (pin "8") (pinfunction "DQ4_8") (pintype "bidirectional"))
    )
    (net (code "31") (name "DRAM_DQ5") (class "Default")
      (node (ref "U1") (pin "78") (pinfunction "PR21A_78") (pintype "passive"))
      (node (ref "U4") (pin "10") (pinfunction "DQ5_10") (pintype "bidirectional"))
    )
    (net (code "32") (name "DRAM_DQ6") (class "Default")
      (node (ref "U1") (pin "81") (pinfunction "PR18B_81") (pintype "passive"))
      (node (ref "U4") (pin "11") (pinfunction "DQ6_11") (pintype "bidirectional"))
    )
    (net (code "33") (name "DRAM_DQ7") (class "Default")
      (node (ref "U1") (pin "82") (pinfunction "PR18A_82") (pintype "passive"))
      (node (ref "U4") (pin "13") (pinfunction "DQ7_13") (pintype "bidirectional"))
    )
    (net (code "34") (name "DRAM_DQ8") (class "Default")
      (node (ref "U1") (pin "55") (pinfunction "PB23A_55") (pintype "passive"))
      (node (ref "U4") (pin "42") (pinfunction "DQ8_42") (pintype "bidirectional"))
    )
    (net (code "35") (name "DRAM_DQ9") (class "Default")
      (node (ref "U1") (pin "54") (pinfunction "PB18B_54") (pintype "passive"))
      (node (ref "U4") (pin "44") (pinfunction "DQ9_44") (pintype "bidirectional"))
    )
    (net (code "36") (name "DRAM_DQ10") (class "Default")
      (node (ref "U1") (pin "52") (pinfunction "PB18A_52") (pintype "passive"))
      (node (ref "U4") (pin "45") (pinfunction "DQ10_45") (pintype "bidirectional"))
    )
    (net (code "37") (name "DRAM_DQ11") (class "Default")
      (node (ref "U1") (pin "50") (pinfunction "PB16B_50") (pintype "passive"))
      (node (ref "U4") (pin "47") (pinfunction "DQ11_47") (pintype "bidirectional"))
    )
    (net (code "38") (name "DRAM_DQ12") (class "Default")
      (node (ref "U1") (pin "49") (pinfunction "PB16A_49") (pintype "passive"))
      (node (ref "U4") (pin "48") (pinfunction "DQ12_48") (pintype "bidirectional"))
    )
    (net (code "39") (name "DRAM_DQ13") (class "Default")
      (node (ref "U1") (pin "48") (pinfunction "PB13B_48") (pintype "passive"))
      (node (ref "U4") (pin "50") (pinfunction "DQ13_50") (pintype "bidirectional"))
    )
    (net (code "40") (name "DRAM_DQ14") (class "Default")
      (node (ref "U1") (pin "47") (pinfunction "PB13A_47") (pintype "passive"))
      (node (ref "U4") (pin "51") (pinfunction "DQ14_51") (pintype "bidirectional"))
    )
    (net (code "41") (name "DRAM_DQ15") (class "Default")
      (node (ref "U1") (pin "43") (pinfunction "PB9B_43") (pintype "passive"))
      (node (ref "U4") (pin "53") (pinfunction "DQ15_53") (pintype "bidirectional"))
    )
    (net (code "42") (name "DRAM_DQM") (class "Default")
      (node (ref "U1") (pin "56") (pinfunction "PB23B_56") (pintype "passive"))
      (node (ref "U4") (pin "39") (pinfunction "DQM_39") (pintype "input"))
    )
    (net (code "43") (name "DRAM_LDQM") (class "Default")
      (node (ref "U1") (pin "83") (pinfunction "PR17B_83") (pintype "passive"))
      (node (ref "U4") (pin "15") (pinfunction "LDQM_15") (pintype "input"))
    )
    (net (code "44") (name "DRAM_RAS") (class "Default")
      (node (ref "U1") (pin "86") (pinfunction "PR16A_86") (pintype "passive"))
      (node (ref "U4") (pin "18") (pinfunction "RAS#_18") (pintype "input"))
    )
    (net (code "45") (name "DRAM_WE") (class "Default")
      (node (ref "U1") (pin "84") (pinfunction "PR17A_84") (pintype "passive"))
      (node (ref "U4") (pin "16") (pinfunction "WE#_16") (pintype "input"))
    )
    (net (code "46") (name "FLASH_CS") (class "Default")
      (node (ref "U1") (pin "17") (pinfunction "PL11B_17") (pintype "passive"))
      (node (ref "U3") (pin "1") (pinfunction "~{CS}_1") (pintype "bidirectional"))
    )
    (net (code "47") (name "FLASH_HOLD") (class "Default")
      (node (ref "U1") (pin "35") (pinfunction "PL25B_35") (pintype "passive"))
      (node (ref "U3") (pin "7") (pinfunction "~{HOLD}(D3)_7") (pintype "bidirectional"))
    )
    (net (code "48") (name "FLASH_SCK") (class "Default")
      (node (ref "U1") (pin "34") (pinfunction "PL25A_34") (pintype "passive"))
      (node (ref "U3") (pin "6") (pinfunction "SCK_6") (pintype "bidirectional"))
    )
    (net (code "49") (name "FLASH_SI") (class "Default")
      (node (ref "U1") (pin "33") (pinfunction "PL24B_33") (pintype "passive"))
      (node (ref "U3") (pin "5") (pinfunction "SI(D0)_5") (pintype "bidirectional"))
    )
    (net (code "50") (name "FLASH_SO") (class "Default")
      (node (ref "U1") (pin "19") (pinfunction "PL12A_19") (pintype "passive"))
      (node (ref "U3") (pin "2") (pinfunction "SO(D1)_2") (pintype "bidirectional"))
    )
    (net (code "51") (name "FLASH_WP") (class "Default")
      (node (ref "U1") (pin "20") (pinfunction "PL12B_20") (pintype "passive"))
      (node (ref "U3") (pin "3") (pinfunction "~{WP}(D2)_3") (pintype "bidirectional"))
    )
    (net (code "52") (name "FPGA_CLOCK") (class "Default")
      (node (ref "R11") (pin "1") (pinfunction "1_1") (pintype "passive"))
      (node (ref "U1") (pin "3") (pinfunction "PL4A_3") (pintype "passive"))
    )
    (net (code "53") (name "GND") (class "Default")
      (node (ref "AUDIO") (pin "SLEEVE") (pinfunction "SLEEVE_SLEEVE") (pintype "bidirectional"))
      (node (ref "C1") (pin "2") (pinfunction "2_2") (pintype "passive"))
      (node (ref "C10") (pin "1") (pinfunction "1_1") (pintype "passive"))
      (node (ref "C11") (pin "2") (pinfunction "2_2") (pintype "passive"))
      (node (ref "C12") (pin "2") (pinfunction "2_2") (pintype "passive"))
      (node (ref "C13") (pin "2") (pinfunction "2_2") (pintype "passive"))
      (node (ref "C14") (pin "2") (pinfunction "2_2") (pintype "passive"))
      (node (ref "C15") (pin "2") (pinfunction "2_2") (pintype "passive"))
      (node (ref "C16") (pin "1") (pinfunction "1_1") (pintype "passive"))
      (node (ref "C17") (pin "2") (pinfunction "2_2") (pintype "passive"))
      (node (ref "C18") (pin "2") (pinfunction "2_2") (pintype "passive"))
      (node (ref "C19") (pin "2") (pinfunction "2_2") (pintype "passive"))
      (node (ref "C2") (pin "2") (pinfunction "2_2") (pintype "passive"))
      (node (ref "C20") (pin "1") (pinfunction "1_1") (pintype "passive"))
      (node (ref "C21") (pin "2") (pinfunction "2_2") (pintype "passive"))
      (node (ref "C22") (pin "2") (pinfunction "2_2") (pintype "passive"))
      (node (ref "C23") (pin "2") (pinfunction "2_2") (pintype "passive"))
      (node (ref "C26") (pin "2") (pinfunction "2_2") (pintype "passive"))
      (node (ref "C27") (pin "2") (pinfunction "2_2") (pintype "passive"))
      (node (ref "C28") (pin "2") (pinfunction "2_2") (pintype "passive"))
      (node (ref "C29") (pin "2") (pinfunction "2_2") (pintype "passive"))
      (node (ref "C3") (pin "2") (pinfunction "2_2") (pintype "passive"))
      (node (ref "C30") (pin "2") (pinfunction "2_2") (pintype "passive"))
      (node (ref "C31") (pin "2") (pinfunction "2_2") (pintype "passive"))
      (node (ref "C32") (pin "2") (pinfunction "2_2") (pintype "passive"))
      (node (ref "C33") (pin "2") (pinfunction "2_2") (pintype "passive"))
      (node (ref "C34") (pin "2") (pinfunction "2_2") (pintype "passive"))
      (node (ref "C35") (pin "2") (pinfunction "2_2") (pintype "passive"))
      (node (ref "C36") (pin "2") (pinfunction "2_2") (pintype "passive"))
      (node (ref "C37") (pin "2") (pinfunction "2_2") (pintype "passive"))
      (node (ref "C4") (pin "2") (pinfunction "2_2") (pintype "passive"))
      (node (ref "C5") (pin "2") (pinfunction "2_2") (pintype "passive"))
      (node (ref "C6") (pin "2") (pinfunction "2_2") (pintype "passive"))
      (node (ref "C7") (pin "2") (pinfunction "2_2") (pintype "passive"))
      (node (ref "C8") (pin "2") (pinfunction "2_2") (pintype "passive"))
      (node (ref "C9") (pin "1") (pinfunction "1_1") (pintype "passive"))
      (node (ref "IC4") (pin "1") (pinfunction "ADJ_1") (pintype "input"))
      (node (ref "JP1") (pin "11") (pinfunction "11_11") (pintype "passive"))
      (node (ref "JP1") (pin "12") (pinfunction "12_12") (pintype "passive"))
      (node (ref "JP2") (pin "1") (pinfunction "1_1") (pintype "passive"))
      (node (ref "JP4") (pin "1") (pinfunction "1_1") (pintype "passive"))
      (node (ref "LED2") (pin "C") (pinfunction "C_C") (pintype "passive"))
      (node (ref "PS/2") (pin "3") (pinfunction "3_3") (pintype "passive"))
      (node (ref "Q1") (pin "2") (pinfunction "GND_2") (pintype "power_in"))
      (node (ref "R14") (pin "1") (pinfunction "1_1") (pintype "passive"))
      (node (ref "R45") (pin "2") (pinfunction "2_2") (pintype "passive"))
      (node (ref "U$1") (pin "3") (pinfunction "GND,PIN3_3") (pintype "bidirectional"))
      (node (ref "U$1") (pin "6") (pinfunction "GND1,PIN6_6") (pintype "bidirectional"))
      (node (ref "U$1") (pin "SHLD1") (pinfunction "SHLD_GND1_SHLD1") (pintype "bidirectional"))
      (node (ref "U$1") (pin "SHLD2") (pinfunction "SHLD_GND2_SHLD2") (pintype "bidirectional"))
      (node (ref "U$12") (pin "P$2") (pinfunction "S_P$2") (pintype "passive"))
      (node (ref "U$2") (pin "18") (pinfunction "GND1_18") (pintype "power_in"))
      (node (ref "U$2") (pin "25") (pinfunction "GND2_25") (pintype "power_in"))
      (node (ref "U$2") (pin "34") (pinfunction "GND3_34") (pintype "power_in"))
      (node (ref "U$2") (pin "45") (pinfunction "AGND_45") (pintype "power_in"))
      (node (ref "U$2") (pin "47") (pinfunction "TEST_47") (pintype "input"))
      (node (ref "U$2") (pin "9") (pinfunction "GND4_9") (pintype "bidirectional"))
      (node (ref "U$4") (pin "25") (pinfunction "25_25") (pintype "passive"))
      (node (ref "U$4") (pin "3") (pinfunction "3_3") (pintype "passive"))
      (node (ref "U$4") (pin "35") (pinfunction "35_35") (pintype "passive"))
      (node (ref "U$4") (pin "4") (pinfunction "4_4") (pintype "passive"))
      (node (ref "U1") (pin "101") (pinfunction "GND_4_101") (pintype "power_in"))
      (node (ref "U1") (pin "116") (pinfunction "GND_5_116") (pintype "power_in"))
      (node (ref "U1") (pin "124") (pinfunction "GND_6_124") (pintype "power_in"))
      (node (ref "U1") (pin "134") (pinfunction "GND_134") (pintype "power_in"))
      (node (ref "U1") (pin "18") (pinfunction "GND_3_18") (pintype "power_in"))
      (node (ref "U1") (pin "29") (pinfunction "GND_4_29") (pintype "power_in"))
      (node (ref "U1") (pin "46") (pinfunction "GND_5_46") (pintype "power_in"))
      (node (ref "U1") (pin "53") (pinfunction "GND_6_53") (pintype "power_in"))
      (node (ref "U1") (pin "64") (pinfunction "GND_64") (pintype "power_in"))
      (node (ref "U1") (pin "8") (pinfunction "GND_2_8") (pintype "power_in"))
      (node (ref "U1") (pin "80") (pinfunction "GND_2_80") (pintype "power_in"))
      (node (ref "U1") (pin "90") (pinfunction "GND_3_90") (pintype "power_in"))
      (node (ref "U2") (pin "GND1") (pinfunction "GND_GND1") (pintype "bidirectional"))
      (node (ref "U3") (pin "4") (pinfunction "GND_4") (pintype "bidirectional"))
      (node (ref "U4") (pin "12") (pinfunction "VSSQ_12") (pintype "power_in"))
      (node (ref "U4") (pin "28") (pinfunction "VSS_28") (pintype "power_in"))
      (node (ref "U4") (pin "41") (pinfunction "VSS_41") (pintype "power_in"))
      (node (ref "U4") (pin "46") (pinfunction "VSSQ_46") (pintype "power_in"))
      (node (ref "U4") (pin "52") (pinfunction "VSSQ_52") (pintype "power_in"))
      (node (ref "U4") (pin "54") (pinfunction "VSS_54") (pintype "power_in"))
      (node (ref "U4") (pin "6") (pinfunction "VSSQ_6") (pintype "power_in"))
      (node (ref "VIDEO") (pin "2") (pinfunction "2_2") (pintype "passive"))
      (node (ref "VIDEO") (pin "2@1") (pinfunction "2_2@1") (pintype "passive"))
      (node (ref "VIDEO") (pin "2@2") (pinfunction "2_2@2") (pintype "passive"))
    )
    (net (code "54") (name "INITN") (class "Default")
      (node (ref "R19") (pin "1") (pinfunction "1_1") (pintype "passive"))
      (node (ref "U1") (pin "110") (pinfunction "PT36C_110") (pintype "passive"))
    )
    (net (code "55") (name "IO3") (class "Default")
      (node (ref "U$4") (pin "5") (pinfunction "5_5") (pintype "passive"))
      (node (ref "U1") (pin "6") (pinfunction "PL6B_6") (pintype "passive"))
    )
    (net (code "56") (name "IO4") (class "Default")
      (node (ref "U$4") (pin "6") (pinfunction "6_6") (pintype "passive"))
      (node (ref "U1") (pin "9") (pinfunction "PL8A_9") (pintype "passive"))
    )
    (net (code "57") (name "IO5") (class "Default")
      (node (ref "U$4") (pin "7") (pinfunction "7_7") (pintype "passive"))
      (node (ref "U1") (pin "10") (pinfunction "PL8B_10") (pintype "passive"))
    )
    (net (code "58") (name "IO6") (class "Default")
      (node (ref "U$4") (pin "8") (pinfunction "8_8") (pintype "passive"))
      (node (ref "U1") (pin "11") (pinfunction "PL9A_11") (pintype "passive"))
    )
    (net (code "59") (name "IO7") (class "Default")
      (node (ref "U$4") (pin "9") (pinfunction "9_9") (pintype "passive"))
      (node (ref "U1") (pin "12") (pinfunction "PL9B_12") (pintype "passive"))
    )
    (net (code "60") (name "IO8") (class "Default")
      (node (ref "U$4") (pin "10") (pinfunction "10_10") (pintype "passive"))
      (node (ref "U1") (pin "13") (pinfunction "PL10A_13") (pintype "passive"))
    )
    (net (code "61") (name "IO9") (class "Default")
      (node (ref "U$4") (pin "11") (pinfunction "11_11") (pintype "passive"))
      (node (ref "U1") (pin "14") (pinfunction "PL10B_14") (pintype "passive"))
    )
    (net (code "62") (name "IO10") (class "Default")
      (node (ref "U$4") (pin "13") (pinfunction "13_13") (pintype "passive"))
      (node (ref "U1") (pin "15") (pinfunction "PL11A_15") (pintype "passive"))
    )
    (net (code "63") (name "IO11") (class "Default")
      (node (ref "U$4") (pin "15") (pinfunction "15_15") (pintype "passive"))
      (node (ref "U1") (pin "23") (pinfunction "PL17A_23") (pintype "passive"))
    )
    (net (code "64") (name "IO12") (class "Default")
      (node (ref "U$4") (pin "17") (pinfunction "17_17") (pintype "passive"))
      (node (ref "U1") (pin "24") (pinfunction "PL17B_24") (pintype "passive"))
    )
    (net (code "65") (name "IO13") (class "Default")
      (node (ref "U$4") (pin "19") (pinfunction "19_19") (pintype "passive"))
      (node (ref "U1") (pin "25") (pinfunction "PL19A_25") (pintype "passive"))
    )
    (net (code "66") (name "IO14") (class "Default")
      (node (ref "U$4") (pin "21") (pinfunction "21_21") (pintype "passive"))
      (node (ref "U1") (pin "26") (pinfunction "PL19B_26") (pintype "passive"))
    )
    (net (code "67") (name "IO15") (class "Default")
      (node (ref "U$4") (pin "27") (pinfunction "27_27") (pintype "passive"))
      (node (ref "U1") (pin "27") (pinfunction "PL22A_27") (pintype "passive"))
    )
    (net (code "68") (name "IO16") (class "Default")
      (node (ref "U$4") (pin "29") (pinfunction "29_29") (pintype "passive"))
      (node (ref "U1") (pin "28") (pinfunction "PL22B_28") (pintype "passive"))
    )
    (net (code "69") (name "IO17") (class "Default")
      (node (ref "U$4") (pin "31") (pinfunction "31_31") (pintype "passive"))
      (node (ref "U1") (pin "31") (pinfunction "PL23D_31") (pintype "passive"))
    )
    (net (code "70") (name "IO18") (class "Default")
      (node (ref "U$4") (pin "33") (pinfunction "33_33") (pintype "passive"))
      (node (ref "U1") (pin "32") (pinfunction "PL24A_32") (pintype "passive"))
    )
    (net (code "71") (name "JTAGENB") (class "Default")
      (node (ref "R22") (pin "1") (pinfunction "1_1") (pintype "passive"))
      (node (ref "U1") (pin "120") (pinfunction "PT27C_120") (pintype "passive"))
    )
    (net (code "72") (name "JTAG_TCK") (class "Default")
      (node (ref "JP1") (pin "7") (pinfunction "7_7") (pintype "passive"))
      (node (ref "U1") (pin "131") (pinfunction "PT17C_131") (pintype "passive"))
    )
    (net (code "73") (name "JTAG_TDI") (class "Default")
      (node (ref "JP1") (pin "5") (pinfunction "5_5") (pintype "passive"))
      (node (ref "U1") (pin "136") (pinfunction "PT14D_136") (pintype "passive"))
    )
    (net (code "74") (name "JTAG_TDO") (class "Default")
      (node (ref "JP1") (pin "3") (pinfunction "3_3") (pintype "passive"))
      (node (ref "U1") (pin "137") (pinfunction "PT14C_137") (pintype "passive"))
    )
    (net (code "75") (name "JTAG_TMS") (class "Default")
      (node (ref "JP1") (pin "9") (pinfunction "9_9") (pintype "passive"))
      (node (ref "U1") (pin "130") (pinfunction "PT17D_130") (pintype "passive"))
    )
    (net (code "76") (name "LED_B") (class "Default")
      (node (ref "R9") (pin "2") (pinfunction "2_2") (pintype "passive"))
      (node (ref "U1") (pin "41") (pinfunction "PB6B_41") (pintype "passive"))
    )
    (net (code "77") (name "LED_G") (class "Default")
      (node (ref "R8") (pin "2") (pinfunction "2_2") (pintype "passive"))
      (node (ref "U1") (pin "42") (pinfunction "PB9A_42") (pintype "passive"))
    )
    (net (code "78") (name "LED_R") (class "Default")
      (node (ref "R10") (pin "2") (pinfunction "2_2") (pintype "passive"))
      (node (ref "U1") (pin "39") (pinfunction "PB4B_39") (pintype "passive"))
    )
    (net (code "79") (name "MS2_CLOCK") (class "Default")
      (node (ref "PS/2") (pin "6") (pinfunction "6_6") (pintype "passive"))
      (node (ref "R24") (pin "2") (pinfunction "2_2") (pintype "passive"))
      (node (ref "U1") (pin "4") (pinfunction "PL4B_4") (pintype "passive"))
    )
    (net (code "80") (name "MS2_DATA") (class "Default")
      (node (ref "PS/2") (pin "2") (pinfunction "2_2") (pintype "passive"))
      (node (ref "R23") (pin "2") (pinfunction "2_2") (pintype "passive"))
      (node (ref "U1") (pin "5") (pinfunction "PL6A_5") (pintype "passive"))
    )
    (net (code "81") (name "Net-(C16-Pad2)") (class "Default")
      (node (ref "C16") (pin "2") (pinfunction "2_2") (pintype "passive"))
      (node (ref "R27") (pin "1") (pinfunction "1_1") (pintype "passive"))
      (node (ref "R28") (pin "1") (pinfunction "1_1") (pintype "passive"))
      (node (ref "R30") (pin "2") (pinfunction "2_2") (pintype "passive"))
    )
    (net (code "82") (name "Net-(C19-Pad1)") (class "Default")
      (node (ref "C19") (pin "1") (pinfunction "1_1") (pintype "passive"))
      (node (ref "R27") (pin "2") (pinfunction "2_2") (pintype "passive"))
      (node (ref "R29") (pin "1") (pinfunction "1_1") (pintype "passive"))
      (node (ref "R31") (pin "2") (pinfunction "2_2") (pintype "passive"))
    )
    (net (code "83") (name "Net-(C24-+)") (class "Default")
      (node (ref "C20") (pin "2") (pinfunction "2_2") (pintype "passive"))
      (node (ref "C24") (pin "A") (pinfunction "+_A") (pintype "passive"))
      (node (ref "R28") (pin "2") (pinfunction "2_2") (pintype "passive"))
    )
    (net (code "84") (name "Net-(C24--)") (class "Default")
      (node (ref "AUDIO") (pin "TIP") (pinfunction "TIP_TIP") (pintype "bidirectional"))
      (node (ref "C24") (pin "C") (pinfunction "-_C") (pintype "passive"))
    )
    (net (code "85") (name "Net-(C25-+)") (class "Default")
      (node (ref "C23") (pin "1") (pinfunction "1_1") (pintype "passive"))
      (node (ref "C25") (pin "A") (pinfunction "+_A") (pintype "passive"))
      (node (ref "R29") (pin "2") (pinfunction "2_2") (pintype "passive"))
    )
    (net (code "86") (name "Net-(C25--)") (class "Default")
      (node (ref "AUDIO") (pin "RING") (pinfunction "RING_RING") (pintype "bidirectional"))
      (node (ref "C25") (pin "C") (pinfunction "-_C") (pintype "passive"))
    )
    (net (code "87") (name "Net-(LED1-CBLUE)") (class "Default")
      (node (ref "LED1") (pin "P$1") (pinfunction "CBLUE_P$1") (pintype "passive"))
      (node (ref "R8") (pin "1") (pinfunction "1_1") (pintype "passive"))
    )
    (net (code "88") (name "Net-(LED1-CGREEN)") (class "Default")
      (node (ref "LED1") (pin "P$2") (pinfunction "CGREEN_P$2") (pintype "passive"))
      (node (ref "R9") (pin "1") (pinfunction "1_1") (pintype "passive"))
    )
    (net (code "89") (name "Net-(LED1-CRED)") (class "Default")
      (node (ref "LED1") (pin "P$4") (pinfunction "CRED_P$4") (pintype "passive"))
      (node (ref "R10") (pin "1") (pinfunction "1_1") (pintype "passive"))
    )
    (net (code "90") (name "Net-(LED2-PadA)") (class "Default")
      (node (ref "LED2") (pin "A") (pinfunction "A_A") (pintype "passive"))
      (node (ref "R47") (pin "2") (pinfunction "2_2") (pintype "passive"))
    )
    (net (code "91") (name "Net-(Q1-GND{slash}NC)") (class "Default")
      (node (ref "Q1") (pin "1") (pinfunction "GND/NC_1") (pintype "power_in"))
      (node (ref "R13") (pin "2") (pinfunction "2_2") (pintype "passive"))
    )
    (net (code "92") (name "Net-(Q1-OUT)") (class "Default")
      (node (ref "Q1") (pin "3") (pinfunction "OUT_3") (pintype "output"))
      (node (ref "R11") (pin "2") (pinfunction "2_2") (pintype "passive"))
    )
    (net (code "93") (name "Net-(R34-Pad2)") (class "Default")
      (node (ref "R34") (pin "2") (pinfunction "2_2") (pintype "passive"))
      (node (ref "R37") (pin "1") (pinfunction "1_1") (pintype "passive"))
      (node (ref "VIDEO") (pin "1") (pinfunction "1_1") (pintype "passive"))
    )
    (net (code "94") (name "Net-(R35-Pad2)") (class "Default")
      (node (ref "R35") (pin "2") (pinfunction "2_2") (pintype "passive"))
      (node (ref "R37") (pin "2") (pinfunction "2_2") (pintype "passive"))
      (node (ref "R38") (pin "1") (pinfunction "1_1") (pintype "passive"))
    )
    (net (code "95") (name "Net-(R36-Pad2)") (class "Default")
      (node (ref "R36") (pin "2") (pinfunction "2_2") (pintype "passive"))
      (node (ref "R38") (pin "2") (pinfunction "2_2") (pintype "passive"))
      (node (ref "R42") (pin "1") (pinfunction "1_1") (pintype "passive"))
    )
    (net (code "96") (name "Net-(R39-Pad2)") (class "Default")
      (node (ref "R39") (pin "2") (pinfunction "2_2") (pintype "passive"))
      (node (ref "R42") (pin "2") (pinfunction "2_2") (pintype "passive"))
      (node (ref "R43") (pin "1") (pinfunction "1_1") (pintype "passive"))
    )
    (net (code "97") (name "Net-(R40-Pad2)") (class "Default")
      (node (ref "R40") (pin "2") (pinfunction "2_2") (pintype "passive"))
      (node (ref "R43") (pin "2") (pinfunction "2_2") (pintype "passive"))
      (node (ref "R44") (pin "1") (pinfunction "1_1") (pintype "passive"))
    )
    (net (code "98") (name "Net-(R41-Pad2)") (class "Default")
      (node (ref "R41") (pin "2") (pinfunction "2_2") (pintype "passive"))
      (node (ref "R44") (pin "2") (pinfunction "2_2") (pintype "passive"))
      (node (ref "R45") (pin "1") (pinfunction "1_1") (pintype "passive"))
    )
    (net (code "99") (name "Net-(U$2-3V3OUT)") (class "Default")
      (node (ref "C13") (pin "1") (pinfunction "1_1") (pintype "passive"))
      (node (ref "U$2") (pin "6") (pinfunction "3V3OUT_6") (pintype "output"))
    )
    (net (code "100") (name "Net-(U$2-AVCC)") (class "Default")
      (node (ref "C14") (pin "1") (pinfunction "1_1") (pintype "passive"))
      (node (ref "R7") (pin "2") (pinfunction "2_2") (pintype "passive"))
      (node (ref "U$2") (pin "46") (pinfunction "AVCC_46") (pintype "bidirectional"))
    )
    (net (code "101") (name "Net-(U$2-EEDATA)") (class "Default")
      (node (ref "R46") (pin "2") (pinfunction "2_2") (pintype "passive"))
      (node (ref "U$2") (pin "2") (pinfunction "EEDATA_2") (pintype "bidirectional"))
    )
    (net (code "102") (name "Net-(U$2-RESET#)") (class "Default")
      (node (ref "R6") (pin "2") (pinfunction "2_2") (pintype "passive"))
      (node (ref "U$2") (pin "4") (pinfunction "RESET#_4") (pintype "bidirectional"))
    )
    (net (code "103") (name "Net-(U$2-RSTOUT#)") (class "Default")
      (node (ref "R5") (pin "1") (pinfunction "1_1") (pintype "passive"))
      (node (ref "U$2") (pin "5") (pinfunction "RSTOUT#_5") (pintype "bidirectional"))
    )
    (net (code "104") (name "Net-(U$2-USBDM)") (class "Default")
      (node (ref "R3") (pin "2") (pinfunction "2_2") (pintype "passive"))
      (node (ref "U$2") (pin "8") (pinfunction "USBDM_8") (pintype "bidirectional"))
    )
    (net (code "105") (name "Net-(U$2-USBDP)") (class "Default")
      (node (ref "R4") (pin "2") (pinfunction "2_2") (pintype "passive"))
      (node (ref "R5") (pin "2") (pinfunction "2_2") (pintype "passive"))
      (node (ref "U$2") (pin "7") (pinfunction "USBDP_7") (pintype "bidirectional"))
    )
    (net (code "106") (name "Net-(U$2-XTIN)") (class "Default")
      (node (ref "C17") (pin "1") (pinfunction "1_1") (pintype "passive"))
      (node (ref "R12") (pin "1") (pinfunction "1_1") (pintype "passive"))
      (node (ref "U$2") (pin "43") (pinfunction "XTIN_43") (pintype "bidirectional"))
      (node (ref "X1") (pin "1") (pinfunction "1_1") (pintype "passive"))
    )
    (net (code "107") (name "Net-(U$2-XTOUT)") (class "Default")
      (node (ref "C18") (pin "1") (pinfunction "1_1") (pintype "passive"))
      (node (ref "R12") (pin "2") (pinfunction "2_2") (pintype "passive"))
      (node (ref "U$2") (pin "44") (pinfunction "XTOUT_44") (pintype "bidirectional"))
      (node (ref "X1") (pin "2") (pinfunction "2_2") (pintype "passive"))
    )
    (net (code "108") (name "Net-(U2-D+)") (class "Default")
      (node (ref "R4") (pin "1") (pinfunction "1_1") (pintype "passive"))
      (node (ref "U2") (pin "D+1") (pinfunction "D+_D+1") (pintype "bidirectional"))
    )
    (net (code "109") (name "Net-(U2-D-)") (class "Default")
      (node (ref "R3") (pin "1") (pinfunction "1_1") (pintype "passive"))
      (node (ref "U2") (pin "D-1") (pinfunction "D-_D-1") (pintype "bidirectional"))
    )
    (net (code "110") (name "PROGRAMN") (class "Default")
      (node (ref "R21") (pin "1") (pinfunction "1_1") (pintype "passive"))
      (node (ref "U1") (pin "119") (pinfunction "PT27D_119") (pintype "passive"))
    )
    (net (code "111") (name "PS2_CLOCK") (class "Default")
      (node (ref "PS/2") (pin "5") (pinfunction "5_5") (pintype "passive"))
      (node (ref "R25") (pin "2") (pinfunction "2_2") (pintype "passive"))
      (node (ref "U1") (pin "2") (pinfunction "PL3B_2") (pintype "passive"))
    )
    (net (code "112") (name "PS2_DATA") (class "Default")
      (node (ref "PS/2") (pin "1") (pinfunction "1_1") (pintype "passive"))
      (node (ref "R26") (pin "2") (pinfunction "2_2") (pintype "passive"))
      (node (ref "U1") (pin "138") (pinfunction "PT11B_138") (pintype "passive"))
    )
    (net (code "113") (name "SCL") (class "Default")
      (node (ref "JP4") (pin "2") (pinfunction "2_2") (pintype "passive"))
      (node (ref "R1") (pin "1") (pinfunction "1_1") (pintype "passive"))
      (node (ref "U1") (pin "126") (pinfunction "PT22C_126") (pintype "passive"))
    )
    (net (code "114") (name "SDA") (class "Default")
      (node (ref "JP4") (pin "3") (pinfunction "3_3") (pintype "passive"))
      (node (ref "R2") (pin "1") (pinfunction "1_1") (pintype "passive"))
      (node (ref "U1") (pin "125") (pinfunction "PT22D_125") (pintype "passive"))
    )
    (net (code "115") (name "SEG_A1") (class "Default")
      (node (ref "U$3") (pin "17") (pinfunction "A1_17") (pintype "bidirectional"))
      (node (ref "U1") (pin "115") (pinfunction "PT28B_115") (pintype "passive"))
    )
    (net (code "116") (name "SEG_A2") (class "Default")
      (node (ref "U$3") (pin "12") (pinfunction "A2_12") (pintype "bidirectional"))
      (node (ref "U1") (pin "127") (pinfunction "PT18B_127") (pintype "passive"))
    )
    (net (code "117") (name "SEG_B1") (class "Default")
      (node (ref "U$3") (pin "16") (pinfunction "B1_16") (pintype "bidirectional"))
      (node (ref "U1") (pin "117") (pinfunction "PT28A_117") (pintype "passive"))
    )
    (net (code "118") (name "SEG_B2") (class "Default")
      (node (ref "U$3") (pin "11") (pinfunction "B2_11") (pintype "bidirectional"))
      (node (ref "U1") (pin "128") (pinfunction "PT18A_128") (pintype "passive"))
    )
    (net (code "119") (name "SEG_C1") (class "Default")
      (node (ref "U$3") (pin "4") (pinfunction "C1_4") (pintype "bidirectional"))
      (node (ref "U1") (pin "103") (pinfunction "PR4C_103") (pintype "passive"))
    )
    (net (code "120") (name "SEG_C2") (class "Default")
      (node (ref "U$3") (pin "9") (pinfunction "C2_9") (pintype "bidirectional"))
      (node (ref "U1") (pin "111") (pinfunction "PT35B_111") (pintype "passive"))
    )
    (net (code "121") (name "SEG_D1") (class "Default")
      (node (ref "U$3") (pin "2") (pinfunction "D1_2") (pintype "bidirectional"))
      (node (ref "U1") (pin "99") (pinfunction "PR5B_99") (pintype "passive"))
    )
    (net (code "122") (name "SEG_D2") (class "Default")
      (node (ref "U$3") (pin "7") (pinfunction "D2_7") (pintype "bidirectional"))
      (node (ref "U1") (pin "106") (pinfunction "PR2B_106") (pintype "passive"))
    )
    (net (code "123") (name "SEG_DIG1") (class "Default")
      (node (ref "U$3") (pin "18") (pinfunction "DIG2_18") (pintype "bidirectional"))
      (node (ref "U$3") (pin "3") (pinfunction "DIG1_3") (pintype "bidirectional"))
      (node (ref "U1") (pin "100") (pinfunction "PR5A_100") (pintype "passive"))
    )
    (net (code "124") (name "SEG_DIG2") (class "Default")
      (node (ref "U$3") (pin "13") (pinfunction "DIG4_13") (pintype "bidirectional"))
      (node (ref "U$3") (pin "8") (pinfunction "DIG3_8") (pintype "bidirectional"))
      (node (ref "U1") (pin "107") (pinfunction "PR2A_107") (pintype "passive"))
    )
    (net (code "125") (name "SEG_DP1") (class "Default")
      (node (ref "U$3") (pin "5") (pinfunction "DP1_5") (pintype "bidirectional"))
      (node (ref "U1") (pin "104") (pinfunction "PR3B_104") (pintype "passive"))
    )
    (net (code "126") (name "SEG_DP2") (class "Default")
      (node (ref "U$3") (pin "10") (pinfunction "DP2_10") (pintype "bidirectional"))
      (node (ref "U1") (pin "112") (pinfunction "PT35A_112") (pintype "passive"))
    )
    (net (code "127") (name "SEG_E1") (class "Default")
      (node (ref "U$3") (pin "1") (pinfunction "E1_1") (pintype "bidirectional"))
      (node (ref "U1") (pin "98") (pinfunction "PR7A_98") (pintype "passive"))
    )
    (net (code "128") (name "SEG_E2") (class "Default")
      (node (ref "U$3") (pin "6") (pinfunction "E2_6") (pintype "bidirectional"))
      (node (ref "U1") (pin "105") (pinfunction "PR3A_105") (pintype "passive"))
    )
    (net (code "129") (name "SEG_F1") (class "Default")
      (node (ref "U$3") (pin "19") (pinfunction "F1_19") (pintype "bidirectional"))
      (node (ref "U1") (pin "114") (pinfunction "PT33A_114") (pintype "passive"))
    )
    (net (code "130") (name "SEG_F2") (class "Default")
      (node (ref "U$3") (pin "14") (pinfunction "F2_14") (pintype "bidirectional"))
      (node (ref "U1") (pin "122") (pinfunction "PT25A_122") (pintype "passive"))
    )
    (net (code "131") (name "SEG_G1") (class "Default")
      (node (ref "U$3") (pin "20") (pinfunction "G1_20") (pintype "bidirectional"))
      (node (ref "U1") (pin "113") (pinfunction "PT33B_113") (pintype "passive"))
    )
    (net (code "132") (name "SEG_G2") (class "Default")
      (node (ref "U$3") (pin "15") (pinfunction "G2_15") (pintype "bidirectional"))
      (node (ref "U1") (pin "121") (pinfunction "PT25B_121") (pintype "passive"))
    )
    (net (code "133") (name "SN") (class "Default")
      (node (ref "R20") (pin "1") (pinfunction "1_1") (pintype "passive"))
      (node (ref "U1") (pin "70") (pinfunction "PB38A_70") (pintype "passive"))
    )
    (net (code "134") (name "SPI_CLK") (class "Default")
      (node (ref "U$1") (pin "5") (pinfunction "SCK,PIN5_5") (pintype "bidirectional"))
      (node (ref "U1") (pin "44") (pinfunction "PB12A_44") (pintype "passive"))
    )
    (net (code "135") (name "SPI_CS") (class "Default")
      (node (ref "U$1") (pin "1") (pinfunction "CS,PIN1_1") (pintype "bidirectional"))
      (node (ref "U1") (pin "40") (pinfunction "PB6A_40") (pintype "passive"))
    )
    (net (code "136") (name "SPI_MISO") (class "Default")
      (node (ref "U$1") (pin "7") (pinfunction "DO,PIN7_7") (pintype "bidirectional"))
      (node (ref "U1") (pin "45") (pinfunction "PB12B_45") (pintype "passive"))
    )
    (net (code "137") (name "SPI_MOSI") (class "Default")
      (node (ref "U$1") (pin "2") (pinfunction "DI,PIN2_2") (pintype "bidirectional"))
      (node (ref "U1") (pin "71") (pinfunction "PB38B_71") (pintype "passive"))
    )
    (net (code "138") (name "UART_RX") (class "Default")
      (node (ref "JP2") (pin "3") (pinfunction "3_3") (pintype "passive"))
      (node (ref "U1") (pin "96") (pinfunction "PR9A_96") (pintype "passive"))
    )
    (net (code "139") (name "UART_TX") (class "Default")
      (node (ref "JP2") (pin "2") (pinfunction "2_2") (pintype "passive"))
      (node (ref "U1") (pin "97") (pinfunction "PR7B_97") (pintype "passive"))
    )
    (net (code "140") (name "USBAURT_TX") (class "Default")
      (node (ref "U$2") (pin "40") (pinfunction "BDBUS0_40") (pintype "output"))
      (node (ref "U1") (pin "133") (pinfunction "PT15A_133") (pintype "passive"))
    )
    (net (code "141") (name "USBJTAG_TCK") (class "Default")
      (node (ref "JP1") (pin "8") (pinfunction "8_8") (pintype "passive"))
      (node (ref "R14") (pin "2") (pinfunction "2_2") (pintype "passive"))
      (node (ref "U$2") (pin "24") (pinfunction "ADBUS0_24") (pintype "bidirectional"))
    )
    (net (code "142") (name "USBJTAG_TDI") (class "Default")
      (node (ref "JP1") (pin "6") (pinfunction "6_6") (pintype "passive"))
      (node (ref "R15") (pin "1") (pinfunction "1_1") (pintype "passive"))
      (node (ref "U$2") (pin "23") (pinfunction "ADBUS1_23") (pintype "bidirectional"))
    )
    (net (code "143") (name "USBJTAG_TDO") (class "Default")
      (node (ref "JP1") (pin "4") (pinfunction "4_4") (pintype "passive"))
      (node (ref "R16") (pin "1") (pinfunction "1_1") (pintype "passive"))
      (node (ref "U$2") (pin "22") (pinfunction "ADBUS2_22") (pintype "bidirectional"))
    )
    (net (code "144") (name "USBJTAG_TMS") (class "Default")
      (node (ref "JP1") (pin "10") (pinfunction "10_10") (pintype "passive"))
      (node (ref "R17") (pin "1") (pinfunction "1_1") (pintype "passive"))
      (node (ref "U$2") (pin "21") (pinfunction "ADBUS3_21") (pintype "bidirectional"))
    )
    (net (code "145") (name "USBUART_RX") (class "Default")
      (node (ref "U$2") (pin "39") (pinfunction "BDBUS1_39") (pintype "input"))
      (node (ref "U1") (pin "132") (pinfunction "PT15B_132") (pintype "passive"))
    )
    (net (code "146") (name "VID0") (class "Default")
      (node (ref "R41") (pin "1") (pinfunction "1_1") (pintype "passive"))
      (node (ref "U1") (pin "142") (pinfunction "PT9B_142") (pintype "passive"))
    )
    (net (code "147") (name "VID1") (class "Default")
      (node (ref "R40") (pin "1") (pinfunction "1_1") (pintype "passive"))
      (node (ref "U1") (pin "143") (pinfunction "PT9A_143") (pintype "passive"))
    )
    (net (code "148") (name "VID2") (class "Default")
      (node (ref "R39") (pin "1") (pinfunction "1_1") (pintype "passive"))
      (node (ref "U1") (pin "1") (pinfunction "PL3A_1") (pintype "passive"))
    )
    (net (code "149") (name "VID3") (class "Default")
      (node (ref "R36") (pin "1") (pinfunction "1_1") (pintype "passive"))
      (node (ref "U1") (pin "141") (pinfunction "PT10A_141") (pintype "passive"))
    )
    (net (code "150") (name "VID4") (class "Default")
      (node (ref "R35") (pin "1") (pinfunction "1_1") (pintype "passive"))
      (node (ref "U1") (pin "140") (pinfunction "PT10B_140") (pintype "passive"))
    )
    (net (code "151") (name "VID5") (class "Default")
      (node (ref "R34") (pin "1") (pinfunction "1_1") (pintype "passive"))
      (node (ref "U1") (pin "139") (pinfunction "PT11A_139") (pintype "passive"))
    )
    (net (code "152") (name "unconnected-(AUDIO-PadRSH)") (class "Default")
      (node (ref "AUDIO") (pin "RSH") (pinfunction "RSH_RSH") (pintype "bidirectional"))
    )
    (net (code "153") (name "unconnected-(AUDIO-PadTSH)") (class "Default")
      (node (ref "AUDIO") (pin "TSH") (pinfunction "TSH_TSH") (pintype "bidirectional"))
    )
    (net (code "154") (name "unconnected-(U$1-IR1Q,PIN8-Pad8)") (class "Default")
      (node (ref "U$1") (pin "8") (pinfunction "IR1Q,PIN8_8") (pintype "bidirectional"))
    )
    (net (code "155") (name "unconnected-(U$1-PIN9-Pad9)") (class "Default")
      (node (ref "U$1") (pin "9") (pinfunction "PIN9_9") (pintype "bidirectional"))
    )
    (net (code "156") (name "unconnected-(U$1-PadCD)") (class "Default")
      (node (ref "U$1") (pin "CD") (pinfunction "CD_CD") (pintype "bidirectional"))
    )
    (net (code "157") (name "unconnected-(U$1-PadWP)") (class "Default")
      (node (ref "U$1") (pin "WP") (pinfunction "WP_WP") (pintype "bidirectional"))
    )
    (net (code "158") (name "unconnected-(U$2-ACBUS0-Pad15)") (class "Default")
      (node (ref "U$2") (pin "15") (pinfunction "ACBUS0_15") (pintype "bidirectional"))
    )
    (net (code "159") (name "unconnected-(U$2-ACBUS1-Pad13)") (class "Default")
      (node (ref "U$2") (pin "13") (pinfunction "ACBUS1_13") (pintype "bidirectional"))
    )
    (net (code "160") (name "unconnected-(U$2-ACBUS2-Pad12)") (class "Default")
      (node (ref "U$2") (pin "12") (pinfunction "ACBUS2_12") (pintype "bidirectional"))
    )
    (net (code "161") (name "unconnected-(U$2-ACBUS3-Pad11)") (class "Default")
      (node (ref "U$2") (pin "11") (pinfunction "ACBUS3_11") (pintype "bidirectional"))
    )
    (net (code "162") (name "unconnected-(U$2-ADBUS4-Pad20)") (class "Default")
      (node (ref "U$2") (pin "20") (pinfunction "ADBUS4_20") (pintype "bidirectional"))
    )
    (net (code "163") (name "unconnected-(U$2-ADBUS5-Pad19)") (class "Default")
      (node (ref "U$2") (pin "19") (pinfunction "ADBUS5_19") (pintype "bidirectional"))
    )
    (net (code "164") (name "unconnected-(U$2-ADBUS6-Pad17)") (class "Default")
      (node (ref "U$2") (pin "17") (pinfunction "ADBUS6_17") (pintype "bidirectional"))
    )
    (net (code "165") (name "unconnected-(U$2-ADBUS7-Pad16)") (class "Default")
      (node (ref "U$2") (pin "16") (pinfunction "ADBUS7_16") (pintype "bidirectional"))
    )
    (net (code "166") (name "unconnected-(U$2-BCBUS0-Pad30)") (class "Default")
      (node (ref "U$2") (pin "30") (pinfunction "BCBUS0_30") (pintype "bidirectional"))
    )
    (net (code "167") (name "unconnected-(U$2-BCBUS1-Pad29)") (class "Default")
      (node (ref "U$2") (pin "29") (pinfunction "BCBUS1_29") (pintype "bidirectional"))
    )
    (net (code "168") (name "unconnected-(U$2-BCBUS2-Pad28)") (class "Default")
      (node (ref "U$2") (pin "28") (pinfunction "BCBUS2_28") (pintype "bidirectional"))
    )
    (net (code "169") (name "unconnected-(U$2-BCBUS3-Pad27)") (class "Default")
      (node (ref "U$2") (pin "27") (pinfunction "BCBUS3_27") (pintype "bidirectional"))
    )
    (net (code "170") (name "unconnected-(U$2-BDBUS2-Pad38)") (class "Default")
      (node (ref "U$2") (pin "38") (pinfunction "BDBUS2_38") (pintype "output"))
    )
    (net (code "171") (name "unconnected-(U$2-BDBUS3-Pad37)") (class "Default")
      (node (ref "U$2") (pin "37") (pinfunction "BDBUS3_37") (pintype "input"))
    )
    (net (code "172") (name "unconnected-(U$2-BDBUS4-Pad36)") (class "Default")
      (node (ref "U$2") (pin "36") (pinfunction "BDBUS4_36") (pintype "output"))
    )
    (net (code "173") (name "unconnected-(U$2-BDBUS5-Pad35)") (class "Default")
      (node (ref "U$2") (pin "35") (pinfunction "BDBUS5_35") (pintype "input"))
    )
    (net (code "174") (name "unconnected-(U$2-BDBUS6-Pad33)") (class "Default")
      (node (ref "U$2") (pin "33") (pinfunction "BDBUS6_33") (pintype "input"))
    )
    (net (code "175") (name "unconnected-(U$2-BDBUS7-Pad32)") (class "Default")
      (node (ref "U$2") (pin "32") (pinfunction "BDBUS7_32") (pintype "input"))
    )
    (net (code "176") (name "unconnected-(U$2-EECS-Pad48)") (class "Default")
      (node (ref "U$2") (pin "48") (pinfunction "EECS_48") (pintype "bidirectional"))
    )
    (net (code "177") (name "unconnected-(U$2-EESK-Pad1)") (class "Default")
      (node (ref "U$2") (pin "1") (pinfunction "EESK_1") (pintype "bidirectional"))
    )
    (net (code "178") (name "unconnected-(U$2-PWEN#-Pad41)") (class "Default")
      (node (ref "U$2") (pin "41") (pinfunction "PWEN#_41") (pintype "bidirectional"))
    )
    (net (code "179") (name "unconnected-(U$2-SI{slash}WUA-Pad10)") (class "Default")
      (node (ref "U$2") (pin "10") (pinfunction "SI/WUA_10") (pintype "bidirectional"))
    )
    (net (code "180") (name "unconnected-(U$2-SI{slash}WUB-Pad26)") (class "Default")
      (node (ref "U$2") (pin "26") (pinfunction "SI/WUB_26") (pintype "bidirectional"))
    )
    (net (code "181") (name "unconnected-(U1B-NC-Pad129)") (class "Default")
      (node (ref "U1") (pin "129") (pinfunction "NC_129") (pintype "no_connect"))
    )
    (net (code "182") (name "unconnected-(U2-USBID-PadID1)") (class "Default")
      (node (ref "U2") (pin "ID1") (pinfunction "USBID_ID1") (pintype "bidirectional"))
    )
    (net (code "183") (name "unconnected-(U4-NC-Pad40)") (class "Default")
      (node (ref "U4") (pin "40") (pinfunction "NC_40") (pintype "no_connect"))
    )
  )
)
